# MainBoard.net
KiCad netlist of a schematic drawn in EAGLE
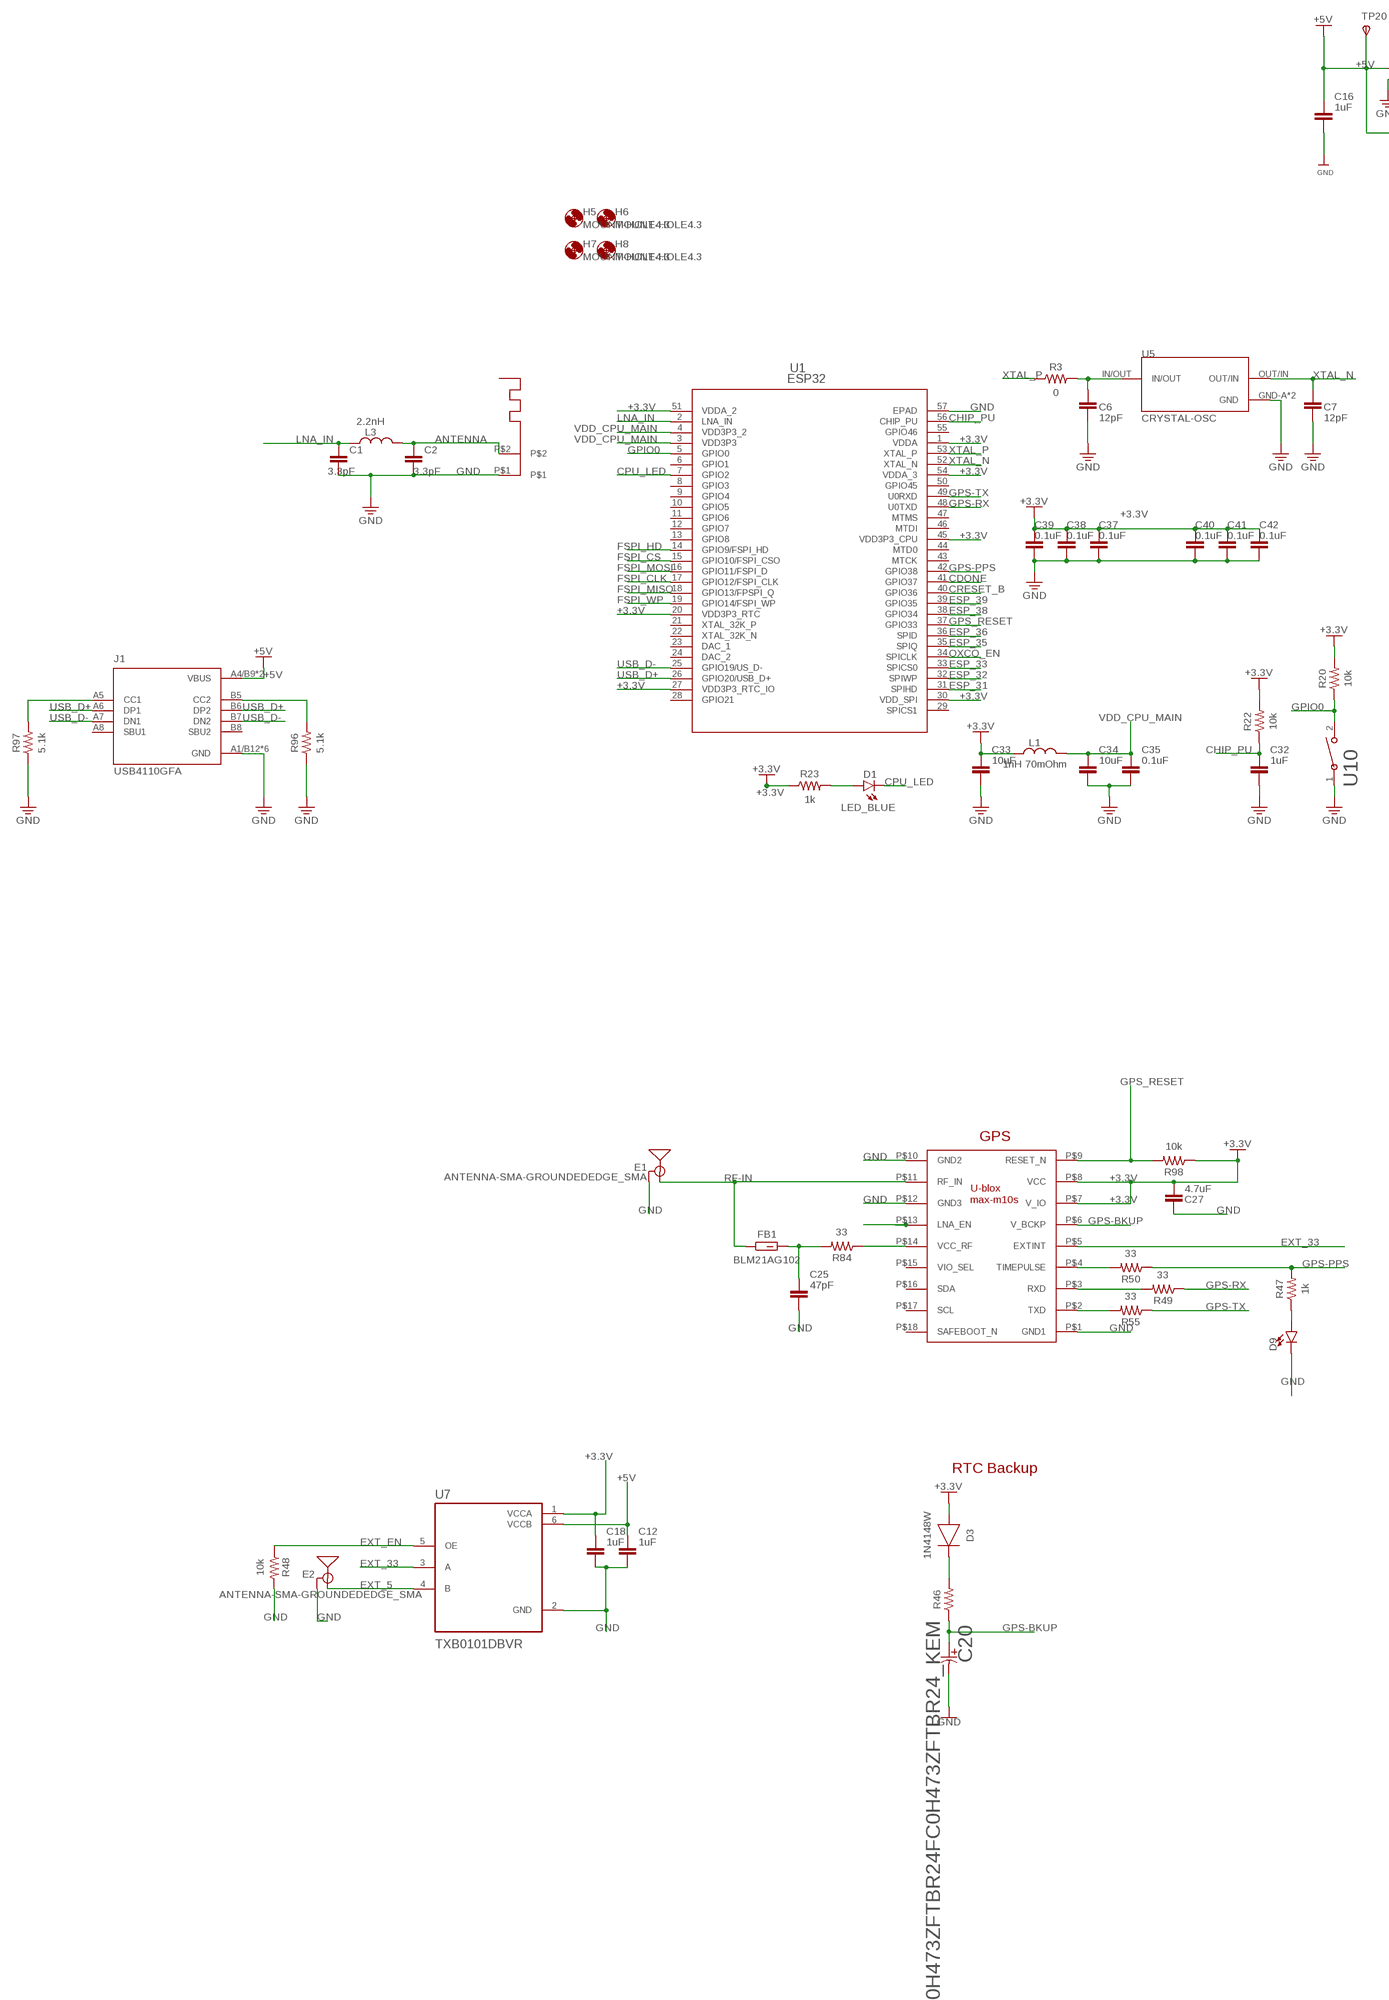
[diagram p0: schematic, sheet 1, part 1 of 2]
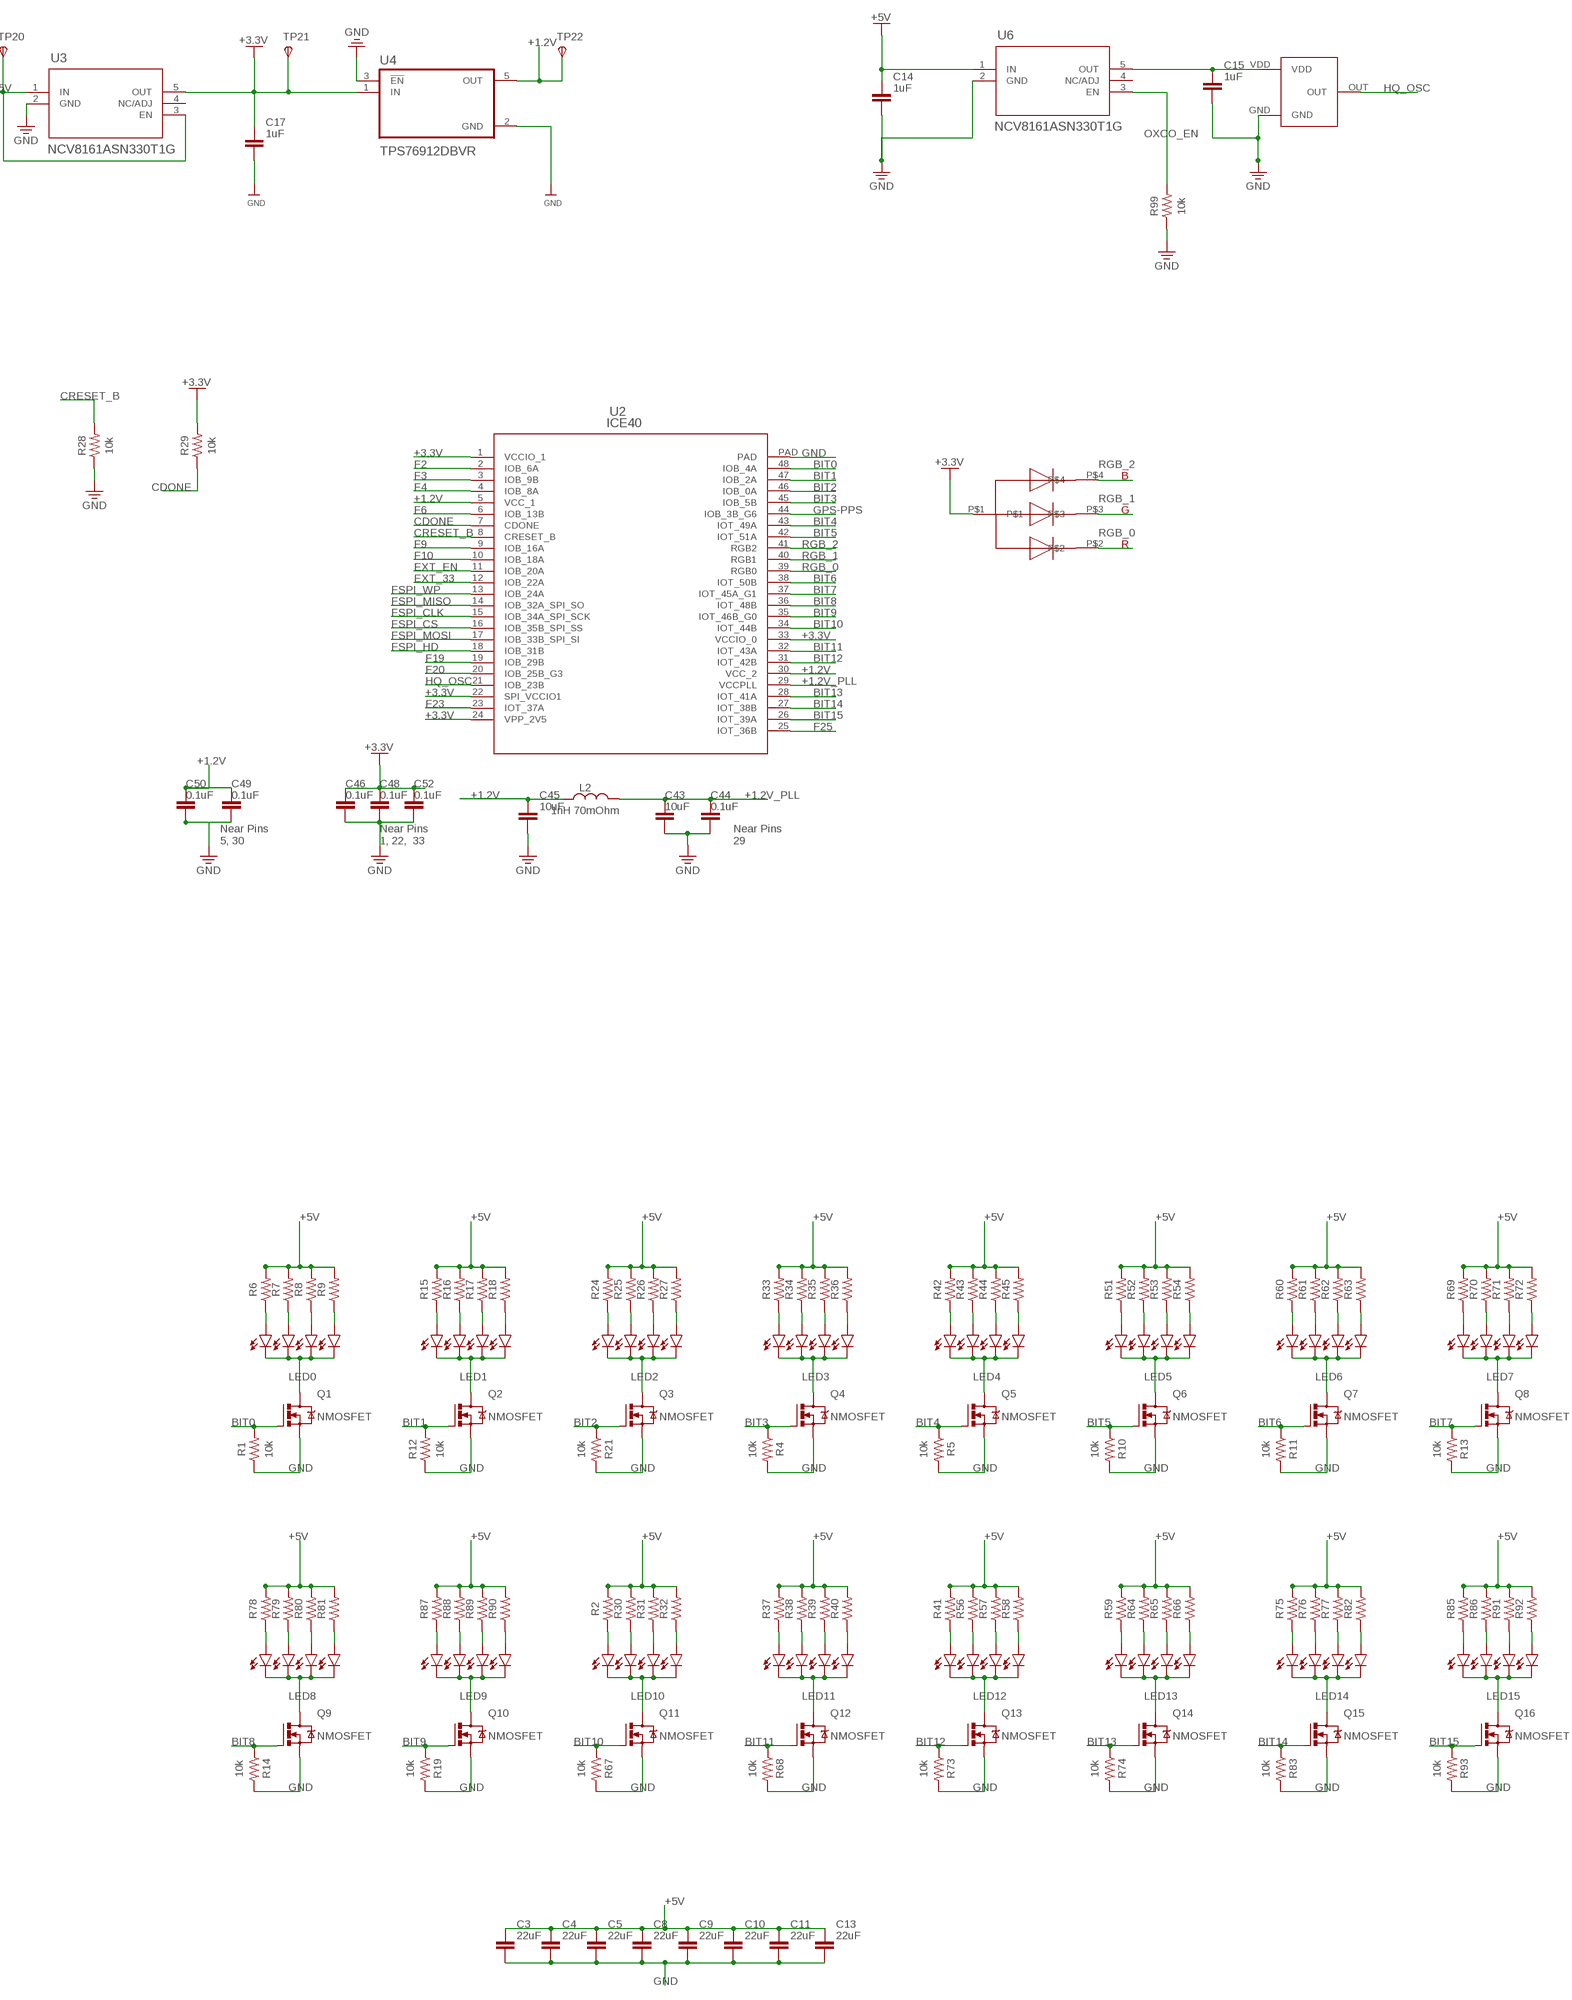
[diagram p1: schematic, sheet 1, part 2 of 2]

(export (version "E")
  (design (tool "Eeschema 10.0.6"))
  (components
    (comp (ref "C1")
      (value "3.3pF")
      (footprint "eagle-import:CAPC1005X60")
      (fields (field (name "LCSC_PART") "C76906"))
      (libsource (lib "eagle-import") (part "CCHIP-0402(1005-METRIC)_"))
    )
    (comp (ref "C2")
      (value "3.3pF")
      (footprint "eagle-import:CAPC1005X60")
      (fields (field (name "LCSC_PART") "C76906"))
      (libsource (lib "eagle-import") (part "CCHIP-0402(1005-METRIC)_"))
    )
    (comp (ref "C3")
      (value "22uF")
      (footprint "eagle-import:CAPC3225X135")
      (fields (field (name "LCSC_PART") "C52306"))
      (libsource (lib "eagle-import") (part "CCHIP-1210(3225-METRIC)_"))
    )
    (comp (ref "C4")
      (value "22uF")
      (footprint "eagle-import:CAPC3225X135")
      (fields (field (name "LCSC_PART") "C52306"))
      (libsource (lib "eagle-import") (part "CCHIP-1210(3225-METRIC)_"))
    )
    (comp (ref "C5")
      (value "22uF")
      (footprint "eagle-import:CAPC3225X135")
      (fields (field (name "LCSC_PART") "C52306"))
      (libsource (lib "eagle-import") (part "CCHIP-1210(3225-METRIC)_"))
    )
    (comp (ref "C6")
      (value "12pF")
      (footprint "eagle-import:CAPC1005X60")
      (fields (field (name "LCSC_PART") "C26406"))
      (libsource (lib "eagle-import") (part "CCHIP-0402(1005-METRIC)_"))
    )
    (comp (ref "C7")
      (value "12pF")
      (footprint "eagle-import:CAPC1005X60")
      (fields (field (name "LCSC_PART") "C26406"))
      (libsource (lib "eagle-import") (part "CCHIP-0402(1005-METRIC)_"))
    )
    (comp (ref "C8")
      (value "22uF")
      (footprint "eagle-import:CAPC3225X135")
      (fields (field (name "LCSC_PART") "C52306"))
      (libsource (lib "eagle-import") (part "CCHIP-1210(3225-METRIC)_"))
    )
    (comp (ref "C9")
      (value "22uF")
      (footprint "eagle-import:CAPC3225X135")
      (fields (field (name "LCSC_PART") "C52306"))
      (libsource (lib "eagle-import") (part "CCHIP-1210(3225-METRIC)_"))
    )
    (comp (ref "C10")
      (value "22uF")
      (footprint "eagle-import:CAPC3225X135")
      (fields (field (name "LCSC_PART") "C52306"))
      (libsource (lib "eagle-import") (part "CCHIP-1210(3225-METRIC)_"))
    )
    (comp (ref "C11")
      (value "22uF")
      (footprint "eagle-import:CAPC3225X135")
      (fields (field (name "LCSC_PART") "C52306"))
      (libsource (lib "eagle-import") (part "CCHIP-1210(3225-METRIC)_"))
    )
    (comp (ref "C12")
      (value "1uF")
      (footprint "eagle-import:CAPC1005X60")
      (fields (field (name "LCSC_PART") "C29266"))
      (libsource (lib "eagle-import") (part "CCHIP-0402(1005-METRIC)_"))
    )
    (comp (ref "C13")
      (value "22uF")
      (footprint "eagle-import:CAPC3225X135")
      (fields (field (name "LCSC_PART") "C52306"))
      (libsource (lib "eagle-import") (part "CCHIP-1210(3225-METRIC)_"))
    )
    (comp (ref "C14")
      (value "1uF")
      (footprint "eagle-import:CAPC2012X110")
      (libsource (lib "eagle-import") (part "CCHIP-0805(2012-METRIC)_"))
    )
    (comp (ref "C15")
      (value "1uF")
      (footprint "eagle-import:CAPC2012X110")
      (libsource (lib "eagle-import") (part "CCHIP-0805(2012-METRIC)_"))
    )
    (comp (ref "C16")
      (value "1uF")
      (footprint "eagle-import:CAPC2012X110")
      (libsource (lib "eagle-import") (part "CCHIP-0805(2012-METRIC)_"))
    )
    (comp (ref "C17")
      (value "1uF")
      (footprint "eagle-import:CAPC2012X110")
      (libsource (lib "eagle-import") (part "CCHIP-0805(2012-METRIC)_"))
    )
    (comp (ref "C18")
      (value "1uF")
      (footprint "eagle-import:CAPC1005X60")
      (fields (field (name "LCSC_PART") "C29266"))
      (libsource (lib "eagle-import") (part "CCHIP-0402(1005-METRIC)_"))
    )
    (comp (ref "C20")
      (value "FC0H473ZFTBR24FC0H473ZFTBR24_KEM")
      (footprint "eagle-import:FC0H473ZFTBR24_KEM")
      (fields
        (field (name "MANUFACTURER_PART_NUMBER") "FC0H473ZFTBR24")
        (field (name "COPYRIGHT") "Copyright (C) 2025 Ultra Librarian. All rights reserved.")
      )
      (libsource (lib "eagle-import") (part "FC0H473ZFTBR24FC0H473ZFTBR24_KEM"))
    )
    (comp (ref "C25")
      (value "47pF")
      (footprint "eagle-import:CAPC1005X60")
      (fields (field (name "LCSC_PART") "C1671"))
      (libsource (lib "eagle-import") (part "CCHIP-0402(1005-METRIC)_"))
    )
    (comp (ref "C27")
      (value "4.7uF")
      (footprint "eagle-import:CAPC1005X60")
      (fields (field (name "LCSC_PART") "C23733"))
      (libsource (lib "eagle-import") (part "CCHIP-0402(1005-METRIC)_"))
    )
    (comp (ref "C32")
      (value "1uF")
      (footprint "eagle-import:CAPC1005X60")
      (fields (field (name "LCSC_PART") "C29266"))
      (libsource (lib "eagle-import") (part "CCHIP-0402(1005-METRIC)_"))
    )
    (comp (ref "C33")
      (value "10uF")
      (footprint "eagle-import:CAPC1005X60")
      (fields (field (name "LCSC_PART") "C76991"))
      (libsource (lib "eagle-import") (part "CCHIP-0402(1005-METRIC)_"))
    )
    (comp (ref "C34")
      (value "10uF")
      (footprint "eagle-import:CAPC1005X60")
      (fields (field (name "LCSC_PART") "C76991"))
      (libsource (lib "eagle-import") (part "CCHIP-0402(1005-METRIC)_"))
    )
    (comp (ref "C35")
      (value "0.1uF")
      (footprint "eagle-import:CAPC1005X60")
      (fields (field (name "LCSC_PART") "C1525"))
      (libsource (lib "eagle-import") (part "CCHIP-0402(1005-METRIC)_"))
    )
    (comp (ref "C37")
      (value "0.1uF")
      (footprint "eagle-import:CAPC1005X60")
      (fields (field (name "LCSC_PART") "C1525"))
      (libsource (lib "eagle-import") (part "CCHIP-0402(1005-METRIC)_"))
    )
    (comp (ref "C38")
      (value "0.1uF")
      (footprint "eagle-import:CAPC1005X60")
      (fields (field (name "LCSC_PART") "C1525"))
      (libsource (lib "eagle-import") (part "CCHIP-0402(1005-METRIC)_"))
    )
    (comp (ref "C39")
      (value "0.1uF")
      (footprint "eagle-import:CAPC1005X60")
      (fields (field (name "LCSC_PART") "C1525"))
      (libsource (lib "eagle-import") (part "CCHIP-0402(1005-METRIC)_"))
    )
    (comp (ref "C40")
      (value "0.1uF")
      (footprint "eagle-import:CAPC1005X60")
      (fields (field (name "LCSC_PART") "C1525"))
      (libsource (lib "eagle-import") (part "CCHIP-0402(1005-METRIC)_"))
    )
    (comp (ref "C41")
      (value "0.1uF")
      (footprint "eagle-import:CAPC1005X60")
      (fields (field (name "LCSC_PART") "C1525"))
      (libsource (lib "eagle-import") (part "CCHIP-0402(1005-METRIC)_"))
    )
    (comp (ref "C42")
      (value "0.1uF")
      (footprint "eagle-import:CAPC1005X60")
      (fields (field (name "LCSC_PART") "C1525"))
      (libsource (lib "eagle-import") (part "CCHIP-0402(1005-METRIC)_"))
    )
    (comp (ref "C43")
      (value "10uF")
      (footprint "eagle-import:CAPC1005X60")
      (fields (field (name "LCSC_PART") "C76991"))
      (libsource (lib "eagle-import") (part "CCHIP-0402(1005-METRIC)_"))
    )
    (comp (ref "C44")
      (value "0.1uF")
      (footprint "eagle-import:CAPC1005X60")
      (fields (field (name "LCSC_PART") "C1525"))
      (libsource (lib "eagle-import") (part "CCHIP-0402(1005-METRIC)_"))
    )
    (comp (ref "C45")
      (value "10uF")
      (footprint "eagle-import:CAPC1005X60")
      (fields (field (name "LCSC_PART") "C76991"))
      (libsource (lib "eagle-import") (part "CCHIP-0402(1005-METRIC)_"))
    )
    (comp (ref "C46")
      (value "0.1uF")
      (footprint "eagle-import:CAPC1005X60")
      (fields (field (name "LCSC_PART") "C1525"))
      (libsource (lib "eagle-import") (part "CCHIP-0402(1005-METRIC)_"))
    )
    (comp (ref "C48")
      (value "0.1uF")
      (footprint "eagle-import:CAPC1005X60")
      (fields (field (name "LCSC_PART") "C1525"))
      (libsource (lib "eagle-import") (part "CCHIP-0402(1005-METRIC)_"))
    )
    (comp (ref "C49")
      (value "0.1uF")
      (footprint "eagle-import:CAPC1005X60")
      (fields (field (name "LCSC_PART") "C1525"))
      (libsource (lib "eagle-import") (part "CCHIP-0402(1005-METRIC)_"))
    )
    (comp (ref "C50")
      (value "0.1uF")
      (footprint "eagle-import:CAPC1005X60")
      (fields (field (name "LCSC_PART") "C1525"))
      (libsource (lib "eagle-import") (part "CCHIP-0402(1005-METRIC)_"))
    )
    (comp (ref "C52")
      (value "0.1uF")
      (footprint "eagle-import:CAPC1005X60")
      (fields (field (name "LCSC_PART") "C1525"))
      (libsource (lib "eagle-import") (part "CCHIP-0402(1005-METRIC)_"))
    )
    (comp (ref "D1")
      (value "LED_BLUE")
      (footprint "eagle-import:LEDC1005X25N_FLAT-B")
      (fields (field (name "LCSC_PART") "C22355736"))
      (libsource (lib "eagle-import") (part "CHIP-FLAT-B_0402"))
    )
    (comp (ref "D2")
      (value "LED_BLUE")
      (footprint "eagle-import:LEDC3216X180N_RND-B")
      (libsource (lib "eagle-import") (part "CHIP-ROUND-B_1206"))
    )
    (comp (ref "D3")
      (value "1N4148W")
      (footprint "eagle-import:SOD3715X135")
      (fields (field (name "MANUFACTURER") "Diodes Incorporated") (field (name "LCSC_PART") "C2128"))
      (libsource (lib "eagle-import") (part "DIODE__SOD123G1N4148W-7-F"))
    )
    (comp (ref "D4")
      (value "LED_BLUE")
      (footprint "eagle-import:LEDC3216X180N_RND-B")
      (fields (field (name "LCSC_PART") "C375482"))
      (libsource (lib "eagle-import") (part "CHIP-ROUND-B_1206"))
    )
    (comp (ref "D5")
      (value "LED_BLUE")
      (footprint "eagle-import:LEDC3216X180N_RND-B")
      (libsource (lib "eagle-import") (part "CHIP-ROUND-B_1206"))
    )
    (comp (ref "D6")
      (value "LED_BLUE")
      (footprint "eagle-import:LEDC3216X180N_RND-B")
      (libsource (lib "eagle-import") (part "CHIP-ROUND-B_1206"))
    )
    (comp (ref "D7")
      (value "LED_BLUE")
      (footprint "eagle-import:LEDC3216X180N_RND-B")
      (libsource (lib "eagle-import") (part "CHIP-ROUND-B_1206"))
    )
    (comp (ref "D8")
      (value "LED_BLUE")
      (footprint "eagle-import:LEDC3216X180N_RND-B")
      (libsource (lib "eagle-import") (part "CHIP-ROUND-B_1206"))
    )
    (comp (ref "D9")
      (value "LED0603")
      (footprint "eagle-import:LED-0603")
      (fields (field (name "LCSC_PART") "C2286"))
      (libsource (lib "eagle-import") (part "LED0603"))
    )
    (comp (ref "D10")
      (value "LED_BLUE")
      (footprint "eagle-import:LEDC3216X180N_RND-B")
      (libsource (lib "eagle-import") (part "CHIP-ROUND-B_1206"))
    )
    (comp (ref "D11")
      (value "LED_BLUE")
      (footprint "eagle-import:LEDC3216X180N_RND-B")
      (libsource (lib "eagle-import") (part "CHIP-ROUND-B_1206"))
    )
    (comp (ref "D12")
      (value "LED_BLUE")
      (footprint "eagle-import:LEDC3216X180N_RND-B")
      (libsource (lib "eagle-import") (part "CHIP-ROUND-B_1206"))
    )
    (comp (ref "D13")
      (value "LED_BLUE")
      (footprint "eagle-import:LEDC3216X180N_RND-B")
      (libsource (lib "eagle-import") (part "CHIP-ROUND-B_1206"))
    )
    (comp (ref "D14")
      (value "LED_BLUE")
      (footprint "eagle-import:LEDC3216X180N_RND-B")
      (libsource (lib "eagle-import") (part "CHIP-ROUND-B_1206"))
    )
    (comp (ref "D15")
      (value "LED_BLUE")
      (footprint "eagle-import:LEDC3216X180N_RND-B")
      (libsource (lib "eagle-import") (part "CHIP-ROUND-B_1206"))
    )
    (comp (ref "D16")
      (value "LED_BLUE")
      (footprint "eagle-import:LEDC3216X180N_RND-B")
      (libsource (lib "eagle-import") (part "CHIP-ROUND-B_1206"))
    )
    (comp (ref "D17")
      (value "LED_BLUE")
      (footprint "eagle-import:LEDC3216X180N_RND-B")
      (libsource (lib "eagle-import") (part "CHIP-ROUND-B_1206"))
    )
    (comp (ref "D18")
      (value "LED_BLUE")
      (footprint "eagle-import:LEDC3216X180N_RND-B")
      (libsource (lib "eagle-import") (part "CHIP-ROUND-B_1206"))
    )
    (comp (ref "D19")
      (value "LED_BLUE")
      (footprint "eagle-import:LEDC3216X180N_RND-B")
      (libsource (lib "eagle-import") (part "CHIP-ROUND-B_1206"))
    )
    (comp (ref "D20")
      (value "LED_BLUE")
      (footprint "eagle-import:LEDC3216X180N_RND-B")
      (libsource (lib "eagle-import") (part "CHIP-ROUND-B_1206"))
    )
    (comp (ref "D21")
      (value "LED_BLUE")
      (footprint "eagle-import:LEDC3216X180N_RND-B")
      (libsource (lib "eagle-import") (part "CHIP-ROUND-B_1206"))
    )
    (comp (ref "D22")
      (value "LED_BLUE")
      (footprint "eagle-import:LEDC3216X180N_RND-B")
      (libsource (lib "eagle-import") (part "CHIP-ROUND-B_1206"))
    )
    (comp (ref "D23")
      (value "LED_BLUE")
      (footprint "eagle-import:LEDC3216X180N_RND-B")
      (libsource (lib "eagle-import") (part "CHIP-ROUND-B_1206"))
    )
    (comp (ref "D24")
      (value "LED_BLUE")
      (footprint "eagle-import:LEDC3216X180N_RND-B")
      (libsource (lib "eagle-import") (part "CHIP-ROUND-B_1206"))
    )
    (comp (ref "D25")
      (value "LED_BLUE")
      (footprint "eagle-import:LEDC3216X180N_RND-B")
      (libsource (lib "eagle-import") (part "CHIP-ROUND-B_1206"))
    )
    (comp (ref "D26")
      (value "LED_BLUE")
      (footprint "eagle-import:LEDC3216X180N_RND-B")
      (libsource (lib "eagle-import") (part "CHIP-ROUND-B_1206"))
    )
    (comp (ref "D27")
      (value "LED_BLUE")
      (footprint "eagle-import:LEDC3216X180N_RND-B")
      (libsource (lib "eagle-import") (part "CHIP-ROUND-B_1206"))
    )
    (comp (ref "D28")
      (value "LED_BLUE")
      (footprint "eagle-import:LEDC3216X180N_RND-B")
      (libsource (lib "eagle-import") (part "CHIP-ROUND-B_1206"))
    )
    (comp (ref "D29")
      (value "LED_BLUE")
      (footprint "eagle-import:LEDC3216X180N_RND-B")
      (libsource (lib "eagle-import") (part "CHIP-ROUND-B_1206"))
    )
    (comp (ref "D30")
      (value "LED_BLUE")
      (footprint "eagle-import:LEDC3216X180N_RND-B")
      (libsource (lib "eagle-import") (part "CHIP-ROUND-B_1206"))
    )
    (comp (ref "D31")
      (value "LED_BLUE")
      (footprint "eagle-import:LEDC3216X180N_RND-B")
      (libsource (lib "eagle-import") (part "CHIP-ROUND-B_1206"))
    )
    (comp (ref "D32")
      (value "LED_BLUE")
      (footprint "eagle-import:LEDC3216X180N_RND-B")
      (libsource (lib "eagle-import") (part "CHIP-ROUND-B_1206"))
    )
    (comp (ref "D33")
      (value "LED_BLUE")
      (footprint "eagle-import:LEDC3216X180N_RND-B")
      (libsource (lib "eagle-import") (part "CHIP-ROUND-B_1206"))
    )
    (comp (ref "D34")
      (value "LED_BLUE")
      (footprint "eagle-import:LEDC3216X180N_RND-B")
      (libsource (lib "eagle-import") (part "CHIP-ROUND-B_1206"))
    )
    (comp (ref "D35")
      (value "LED_BLUE")
      (footprint "eagle-import:LEDC3216X180N_RND-B")
      (libsource (lib "eagle-import") (part "CHIP-ROUND-B_1206"))
    )
    (comp (ref "D36")
      (value "LED_BLUE")
      (footprint "eagle-import:LEDC3216X180N_RND-B")
      (libsource (lib "eagle-import") (part "CHIP-ROUND-B_1206"))
    )
    (comp (ref "D37")
      (value "LED_BLUE")
      (footprint "eagle-import:LEDC3216X180N_RND-B")
      (libsource (lib "eagle-import") (part "CHIP-ROUND-B_1206"))
    )
    (comp (ref "D38")
      (value "LED_BLUE")
      (footprint "eagle-import:LEDC3216X180N_RND-B")
      (libsource (lib "eagle-import") (part "CHIP-ROUND-B_1206"))
    )
    (comp (ref "D39")
      (value "LED_BLUE")
      (footprint "eagle-import:LEDC3216X180N_RND-B")
      (libsource (lib "eagle-import") (part "CHIP-ROUND-B_1206"))
    )
    (comp (ref "D40")
      (value "LED_BLUE")
      (footprint "eagle-import:LEDC3216X180N_RND-B")
      (libsource (lib "eagle-import") (part "CHIP-ROUND-B_1206"))
    )
    (comp (ref "D41")
      (value "LED_BLUE")
      (footprint "eagle-import:LEDC3216X180N_RND-B")
      (libsource (lib "eagle-import") (part "CHIP-ROUND-B_1206"))
    )
    (comp (ref "D42")
      (value "LED_BLUE")
      (footprint "eagle-import:LEDC3216X180N_RND-B")
      (libsource (lib "eagle-import") (part "CHIP-ROUND-B_1206"))
    )
    (comp (ref "D43")
      (value "LED_BLUE")
      (footprint "eagle-import:LEDC3216X180N_RND-B")
      (libsource (lib "eagle-import") (part "CHIP-ROUND-B_1206"))
    )
    (comp (ref "D44")
      (value "LED_BLUE")
      (footprint "eagle-import:LEDC3216X180N_RND-B")
      (libsource (lib "eagle-import") (part "CHIP-ROUND-B_1206"))
    )
    (comp (ref "D45")
      (value "LED_BLUE")
      (footprint "eagle-import:LEDC3216X180N_RND-B")
      (libsource (lib "eagle-import") (part "CHIP-ROUND-B_1206"))
    )
    (comp (ref "D46")
      (value "LED_BLUE")
      (footprint "eagle-import:LEDC3216X180N_RND-B")
      (libsource (lib "eagle-import") (part "CHIP-ROUND-B_1206"))
    )
    (comp (ref "D47")
      (value "LED_BLUE")
      (footprint "eagle-import:LEDC3216X180N_RND-B")
      (libsource (lib "eagle-import") (part "CHIP-ROUND-B_1206"))
    )
    (comp (ref "D48")
      (value "LED_BLUE")
      (footprint "eagle-import:LEDC3216X180N_RND-B")
      (libsource (lib "eagle-import") (part "CHIP-ROUND-B_1206"))
    )
    (comp (ref "D49")
      (value "LED_BLUE")
      (footprint "eagle-import:LEDC3216X180N_RND-B")
      (libsource (lib "eagle-import") (part "CHIP-ROUND-B_1206"))
    )
    (comp (ref "D50")
      (value "LED_BLUE")
      (footprint "eagle-import:LEDC3216X180N_RND-B")
      (libsource (lib "eagle-import") (part "CHIP-ROUND-B_1206"))
    )
    (comp (ref "D51")
      (value "LED_BLUE")
      (footprint "eagle-import:LEDC3216X180N_RND-B")
      (libsource (lib "eagle-import") (part "CHIP-ROUND-B_1206"))
    )
    (comp (ref "D52")
      (value "LED_BLUE")
      (footprint "eagle-import:LEDC3216X180N_RND-B")
      (libsource (lib "eagle-import") (part "CHIP-ROUND-B_1206"))
    )
    (comp (ref "D53")
      (value "LED_BLUE")
      (footprint "eagle-import:LEDC3216X180N_RND-B")
      (libsource (lib "eagle-import") (part "CHIP-ROUND-B_1206"))
    )
    (comp (ref "D54")
      (value "LED_BLUE")
      (footprint "eagle-import:LEDC3216X180N_RND-B")
      (libsource (lib "eagle-import") (part "CHIP-ROUND-B_1206"))
    )
    (comp (ref "D55")
      (value "LED_BLUE")
      (footprint "eagle-import:LEDC3216X180N_RND-B")
      (libsource (lib "eagle-import") (part "CHIP-ROUND-B_1206"))
    )
    (comp (ref "D60")
      (value "LED_BLUE")
      (footprint "eagle-import:LEDC3216X180N_RND-B")
      (libsource (lib "eagle-import") (part "CHIP-ROUND-B_1206"))
    )
    (comp (ref "D61")
      (value "LED_BLUE")
      (footprint "eagle-import:LEDC3216X180N_RND-B")
      (libsource (lib "eagle-import") (part "CHIP-ROUND-B_1206"))
    )
    (comp (ref "D62")
      (value "LED_BLUE")
      (footprint "eagle-import:LEDC3216X180N_RND-B")
      (libsource (lib "eagle-import") (part "CHIP-ROUND-B_1206"))
    )
    (comp (ref "D63")
      (value "LED_BLUE")
      (footprint "eagle-import:LEDC3216X180N_RND-B")
      (libsource (lib "eagle-import") (part "CHIP-ROUND-B_1206"))
    )
    (comp (ref "D68")
      (value "LED_BLUE")
      (footprint "eagle-import:LEDC3216X180N_RND-B")
      (libsource (lib "eagle-import") (part "CHIP-ROUND-B_1206"))
    )
    (comp (ref "D69")
      (value "LED_BLUE")
      (footprint "eagle-import:LEDC3216X180N_RND-B")
      (libsource (lib "eagle-import") (part "CHIP-ROUND-B_1206"))
    )
    (comp (ref "D70")
      (value "LED_BLUE")
      (footprint "eagle-import:LEDC3216X180N_RND-B")
      (libsource (lib "eagle-import") (part "CHIP-ROUND-B_1206"))
    )
    (comp (ref "D71")
      (value "LED_BLUE")
      (footprint "eagle-import:LEDC3216X180N_RND-B")
      (libsource (lib "eagle-import") (part "CHIP-ROUND-B_1206"))
    )
    (comp (ref "D76")
      (value "LED_BLUE")
      (footprint "eagle-import:LEDC3216X180N_RND-B")
      (libsource (lib "eagle-import") (part "CHIP-ROUND-B_1206"))
    )
    (comp (ref "D77")
      (value "LED_BLUE")
      (footprint "eagle-import:LEDC3216X180N_RND-B")
      (libsource (lib "eagle-import") (part "CHIP-ROUND-B_1206"))
    )
    (comp (ref "D78")
      (value "LED_BLUE")
      (footprint "eagle-import:LEDC3216X180N_RND-B")
      (libsource (lib "eagle-import") (part "CHIP-ROUND-B_1206"))
    )
    (comp (ref "D79")
      (value "LED_BLUE")
      (footprint "eagle-import:LEDC3216X180N_RND-B")
      (libsource (lib "eagle-import") (part "CHIP-ROUND-B_1206"))
    )
    (comp (ref "E1")
      (value "ANTENNA-SMA-GROUNDEDEDGE_SMA")
      (footprint "eagle-import:SMA-EDGE")
      (libsource (lib "eagle-import") (part "ANTENNA-SMA-GROUNDEDEDGE_SMA"))
    )
    (comp (ref "E2")
      (value "ANTENNA-SMA-GROUNDEDEDGE_SMA")
      (footprint "eagle-import:SMA-EDGE")
      (libsource (lib "eagle-import") (part "ANTENNA-SMA-GROUNDEDEDGE_SMA"))
    )
    (comp (ref "FB1")
      (value "BLM21AG102")
      (footprint "eagle-import:BEADC2012X105N")
      (fields (field (name "MANUFACTURER") "Murata Electronics") (field (name "LCSC_PART") "C76817"))
      (libsource (lib "eagle-import") (part "FB__0805(2012)BLM21AG102SN1D"))
    )
    (comp (ref "H5")
      (value "MOUNT-HOLE4.3")
      (footprint "eagle-import:4,3")
      (libsource (lib "eagle-import") (part "MOUNT-HOLE4.3"))
    )
    (comp (ref "H6")
      (value "MOUNT-HOLE4.3")
      (footprint "eagle-import:4,3")
      (libsource (lib "eagle-import") (part "MOUNT-HOLE4.3"))
    )
    (comp (ref "H7")
      (value "MOUNT-HOLE4.3")
      (footprint "eagle-import:4,3")
      (libsource (lib "eagle-import") (part "MOUNT-HOLE4.3"))
    )
    (comp (ref "H8")
      (value "MOUNT-HOLE4.3")
      (footprint "eagle-import:4,3")
      (libsource (lib "eagle-import") (part "MOUNT-HOLE4.3"))
    )
    (comp (ref "J1")
      (value "USB4110GFA")
      (footprint "eagle-import:GCT_USB4110GFA")
      (fields (field (name "MF") "GCT") (field (name "LCSC_PART") "C34260841"))
      (libsource (lib "eagle-import") (part "USB4110GFA"))
    )
    (comp (ref "L1")
      (value "1nH 70mOhm")
      (footprint "eagle-import:INDC1006X60N")
      (fields (field (name "MPN") "BLM18KG101TN1D") (field (name "LCSC_PART") "C18222"))
      (libsource (lib "eagle-import") (part "LCHIP-0402(1006-METRIC)_"))
    )
    (comp (ref "L2")
      (value "1nH 70mOhm")
      (footprint "eagle-import:INDC1006X60N")
      (fields (field (name "MPN") "BLM18KG101TN1D") (field (name "LCSC_PART") "C18222"))
      (libsource (lib "eagle-import") (part "LCHIP-0402(1006-METRIC)_"))
    )
    (comp (ref "L3")
      (value "2.2nH")
      (footprint "eagle-import:INDC1006X60N")
      (fields (field (name "MPN") "BLM18KG101TN1D") (field (name "LCSC_PART") "C86061"))
      (libsource (lib "eagle-import") (part "LCHIP-0402(1006-METRIC)_"))
    )
    (comp (ref "Q1")
      (value "NMOSFET")
      (footprint "eagle-import:SOT23")
      (fields (field (name "LCSC_PART") "C478010"))
      (libsource (lib "eagle-import") (part "NMOSFETSOT23-GSD"))
    )
    (comp (ref "Q2")
      (value "NMOSFET")
      (footprint "eagle-import:SOT23")
      (fields (field (name "LCSC_PART") "C478010"))
      (libsource (lib "eagle-import") (part "NMOSFETSOT23-GSD"))
    )
    (comp (ref "Q3")
      (value "NMOSFET")
      (footprint "eagle-import:SOT23")
      (fields (field (name "LCSC_PART") "C478010"))
      (libsource (lib "eagle-import") (part "NMOSFETSOT23-GSD"))
    )
    (comp (ref "Q4")
      (value "NMOSFET")
      (footprint "eagle-import:SOT23")
      (fields (field (name "LCSC_PART") "C478010"))
      (libsource (lib "eagle-import") (part "NMOSFETSOT23-GSD"))
    )
    (comp (ref "Q5")
      (value "NMOSFET")
      (footprint "eagle-import:SOT23")
      (fields (field (name "LCSC_PART") "C478010"))
      (libsource (lib "eagle-import") (part "NMOSFETSOT23-GSD"))
    )
    (comp (ref "Q6")
      (value "NMOSFET")
      (footprint "eagle-import:SOT23")
      (fields (field (name "LCSC_PART") "C478010"))
      (libsource (lib "eagle-import") (part "NMOSFETSOT23-GSD"))
    )
    (comp (ref "Q7")
      (value "NMOSFET")
      (footprint "eagle-import:SOT23")
      (fields (field (name "LCSC_PART") "C478010"))
      (libsource (lib "eagle-import") (part "NMOSFETSOT23-GSD"))
    )
    (comp (ref "Q8")
      (value "NMOSFET")
      (footprint "eagle-import:SOT23")
      (fields (field (name "LCSC_PART") "C478010"))
      (libsource (lib "eagle-import") (part "NMOSFETSOT23-GSD"))
    )
    (comp (ref "Q9")
      (value "NMOSFET")
      (footprint "eagle-import:SOT23")
      (fields (field (name "LCSC_PART") "C478010"))
      (libsource (lib "eagle-import") (part "NMOSFETSOT23-GSD"))
    )
    (comp (ref "Q10")
      (value "NMOSFET")
      (footprint "eagle-import:SOT23")
      (fields (field (name "LCSC_PART") "C478010"))
      (libsource (lib "eagle-import") (part "NMOSFETSOT23-GSD"))
    )
    (comp (ref "Q11")
      (value "NMOSFET")
      (footprint "eagle-import:SOT23")
      (fields (field (name "LCSC_PART") "C478010"))
      (libsource (lib "eagle-import") (part "NMOSFETSOT23-GSD"))
    )
    (comp (ref "Q12")
      (value "NMOSFET")
      (footprint "eagle-import:SOT23")
      (fields (field (name "LCSC_PART") "C478010"))
      (libsource (lib "eagle-import") (part "NMOSFETSOT23-GSD"))
    )
    (comp (ref "Q13")
      (value "NMOSFET")
      (footprint "eagle-import:SOT23")
      (fields (field (name "LCSC_PART") "C478010"))
      (libsource (lib "eagle-import") (part "NMOSFETSOT23-GSD"))
    )
    (comp (ref "Q14")
      (value "NMOSFET")
      (footprint "eagle-import:SOT23")
      (fields (field (name "LCSC_PART") "C478010"))
      (libsource (lib "eagle-import") (part "NMOSFETSOT23-GSD"))
    )
    (comp (ref "Q15")
      (value "NMOSFET")
      (footprint "eagle-import:SOT23")
      (fields (field (name "LCSC_PART") "C478010"))
      (libsource (lib "eagle-import") (part "NMOSFETSOT23-GSD"))
    )
    (comp (ref "Q16")
      (value "NMOSFET")
      (footprint "eagle-import:SOT23")
      (fields (field (name "LCSC_PART") "C478010"))
      (libsource (lib "eagle-import") (part "NMOSFETSOT23-GSD"))
    )
    (comp (ref "R1")
      (value "10k")
      (footprint "eagle-import:RESC2012X65")
      (fields (field (name "LCSC_PART") "C60490"))
      (libsource (lib "eagle-import") (part "Resistor_16378527_R-USCHIP-0805(2012-METRIC)_"))
    )
    (comp (ref "R2")
      (value "R-US_CHIP-0805(2012-METRIC)")
      (footprint "eagle-import:RESC2012X65")
      (libsource (lib "eagle-import") (part "R-USCHIP-0805(2012-METRIC)_"))
    )
    (comp (ref "R3")
      (value "0")
      (footprint "eagle-import:RESC1005X40")
      (fields (field (name "LCSC_PART") "C17168"))
      (libsource (lib "eagle-import") (part "Resistor_16378527_R-USCHIP-0402(1005-METRIC)_"))
    )
    (comp (ref "R4")
      (value "10k")
      (footprint "eagle-import:RESC2012X65")
      (fields (field (name "LCSC_PART") "C60490"))
      (libsource (lib "eagle-import") (part "Resistor_16378527_R-USCHIP-0805(2012-METRIC)_"))
    )
    (comp (ref "R5")
      (value "10k")
      (footprint "eagle-import:RESC2012X65")
      (fields (field (name "LCSC_PART") "C60490"))
      (libsource (lib "eagle-import") (part "Resistor_16378527_R-USCHIP-0805(2012-METRIC)_"))
    )
    (comp (ref "R6")
      (value "R-US_CHIP-0805(2012-METRIC)")
      (footprint "eagle-import:RESC2012X65")
      (libsource (lib "eagle-import") (part "R-USCHIP-0805(2012-METRIC)_"))
    )
    (comp (ref "R7")
      (value "R-US_CHIP-0805(2012-METRIC)")
      (footprint "eagle-import:RESC2012X65")
      (libsource (lib "eagle-import") (part "R-USCHIP-0805(2012-METRIC)_"))
    )
    (comp (ref "R8")
      (value "R-US_CHIP-0805(2012-METRIC)")
      (footprint "eagle-import:RESC2012X65")
      (libsource (lib "eagle-import") (part "R-USCHIP-0805(2012-METRIC)_"))
    )
    (comp (ref "R9")
      (value "R-US_CHIP-0805(2012-METRIC)")
      (footprint "eagle-import:RESC2012X65")
      (libsource (lib "eagle-import") (part "R-USCHIP-0805(2012-METRIC)_"))
    )
    (comp (ref "R10")
      (value "10k")
      (footprint "eagle-import:RESC2012X65")
      (fields (field (name "LCSC_PART") "C60490"))
      (libsource (lib "eagle-import") (part "Resistor_16378527_R-USCHIP-0805(2012-METRIC)_"))
    )
    (comp (ref "R11")
      (value "10k")
      (footprint "eagle-import:RESC2012X65")
      (fields (field (name "LCSC_PART") "C60490"))
      (libsource (lib "eagle-import") (part "Resistor_16378527_R-USCHIP-0805(2012-METRIC)_"))
    )
    (comp (ref "R12")
      (value "10k")
      (footprint "eagle-import:RESC2012X65")
      (fields (field (name "LCSC_PART") "C60490"))
      (libsource (lib "eagle-import") (part "Resistor_16378527_R-USCHIP-0805(2012-METRIC)_"))
    )
    (comp (ref "R13")
      (value "10k")
      (footprint "eagle-import:RESC2012X65")
      (fields (field (name "LCSC_PART") "C60490"))
      (libsource (lib "eagle-import") (part "Resistor_16378527_R-USCHIP-0805(2012-METRIC)_"))
    )
    (comp (ref "R14")
      (value "10k")
      (footprint "eagle-import:RESC2012X65")
      (fields (field (name "LCSC_PART") "C60490"))
      (libsource (lib "eagle-import") (part "Resistor_16378527_R-USCHIP-0805(2012-METRIC)_"))
    )
    (comp (ref "R15")
      (value "R-US_CHIP-0805(2012-METRIC)")
      (footprint "eagle-import:RESC2012X65")
      (libsource (lib "eagle-import") (part "R-USCHIP-0805(2012-METRIC)_"))
    )
    (comp (ref "R16")
      (value "R-US_CHIP-0805(2012-METRIC)")
      (footprint "eagle-import:RESC2012X65")
      (libsource (lib "eagle-import") (part "R-USCHIP-0805(2012-METRIC)_"))
    )
    (comp (ref "R17")
      (value "R-US_CHIP-0805(2012-METRIC)")
      (footprint "eagle-import:RESC2012X65")
      (libsource (lib "eagle-import") (part "R-USCHIP-0805(2012-METRIC)_"))
    )
    (comp (ref "R18")
      (value "R-US_CHIP-0805(2012-METRIC)")
      (footprint "eagle-import:RESC2012X65")
      (libsource (lib "eagle-import") (part "R-USCHIP-0805(2012-METRIC)_"))
    )
    (comp (ref "R19")
      (value "10k")
      (footprint "eagle-import:RESC2012X65")
      (fields (field (name "LCSC_PART") "C60490"))
      (libsource (lib "eagle-import") (part "Resistor_16378527_R-USCHIP-0805(2012-METRIC)_"))
    )
    (comp (ref "R20")
      (value "10k")
      (footprint "eagle-import:RESC1005X40")
      (fields (field (name "LCSC_PART") "C60490"))
      (libsource (lib "eagle-import") (part "Resistor_16378527_R-USCHIP-0402(1005-METRIC)_"))
    )
    (comp (ref "R21")
      (value "10k")
      (footprint "eagle-import:RESC2012X65")
      (fields (field (name "LCSC_PART") "C60490"))
      (libsource (lib "eagle-import") (part "Resistor_16378527_R-USCHIP-0805(2012-METRIC)_"))
    )
    (comp (ref "R22")
      (value "10k")
      (footprint "eagle-import:RESC1005X40")
      (fields (field (name "LCSC_PART") "C60490"))
      (libsource (lib "eagle-import") (part "Resistor_16378527_R-USCHIP-0402(1005-METRIC)_"))
    )
    (comp (ref "R23")
      (value "1k")
      (footprint "eagle-import:RESC1005X40")
      (fields (field (name "LCSC_PART") "C11702"))
      (libsource (lib "eagle-import") (part "Resistor_16378527_R-USCHIP-0402(1005-METRIC)_"))
    )
    (comp (ref "R24")
      (value "R-US_CHIP-0805(2012-METRIC)")
      (footprint "eagle-import:RESC2012X65")
      (libsource (lib "eagle-import") (part "R-USCHIP-0805(2012-METRIC)_"))
    )
    (comp (ref "R25")
      (value "R-US_CHIP-0805(2012-METRIC)")
      (footprint "eagle-import:RESC2012X65")
      (libsource (lib "eagle-import") (part "R-USCHIP-0805(2012-METRIC)_"))
    )
    (comp (ref "R26")
      (value "R-US_CHIP-0805(2012-METRIC)")
      (footprint "eagle-import:RESC2012X65")
      (libsource (lib "eagle-import") (part "R-USCHIP-0805(2012-METRIC)_"))
    )
    (comp (ref "R27")
      (value "R-US_CHIP-0805(2012-METRIC)")
      (footprint "eagle-import:RESC2012X65")
      (libsource (lib "eagle-import") (part "R-USCHIP-0805(2012-METRIC)_"))
    )
    (comp (ref "R28")
      (value "10k")
      (footprint "eagle-import:RESC1005X40")
      (fields (field (name "LCSC_PART") "C60490"))
      (libsource (lib "eagle-import") (part "Resistor_16378527_R-USCHIP-0402(1005-METRIC)_"))
    )
    (comp (ref "R29")
      (value "10k")
      (footprint "eagle-import:RESC1005X40")
      (fields (field (name "LCSC_PART") "C60490"))
      (libsource (lib "eagle-import") (part "Resistor_16378527_R-USCHIP-0402(1005-METRIC)_"))
    )
    (comp (ref "R30")
      (value "R-US_CHIP-0805(2012-METRIC)")
      (footprint "eagle-import:RESC2012X65")
      (libsource (lib "eagle-import") (part "R-USCHIP-0805(2012-METRIC)_"))
    )
    (comp (ref "R31")
      (value "R-US_CHIP-0805(2012-METRIC)")
      (footprint "eagle-import:RESC2012X65")
      (libsource (lib "eagle-import") (part "R-USCHIP-0805(2012-METRIC)_"))
    )
    (comp (ref "R32")
      (value "R-US_CHIP-0805(2012-METRIC)")
      (footprint "eagle-import:RESC2012X65")
      (libsource (lib "eagle-import") (part "R-USCHIP-0805(2012-METRIC)_"))
    )
    (comp (ref "R33")
      (value "R-US_CHIP-0805(2012-METRIC)")
      (footprint "eagle-import:RESC2012X65")
      (libsource (lib "eagle-import") (part "R-USCHIP-0805(2012-METRIC)_"))
    )
    (comp (ref "R34")
      (value "R-US_CHIP-0805(2012-METRIC)")
      (footprint "eagle-import:RESC2012X65")
      (libsource (lib "eagle-import") (part "R-USCHIP-0805(2012-METRIC)_"))
    )
    (comp (ref "R35")
      (value "R-US_CHIP-0805(2012-METRIC)")
      (footprint "eagle-import:RESC2012X65")
      (libsource (lib "eagle-import") (part "R-USCHIP-0805(2012-METRIC)_"))
    )
    (comp (ref "R36")
      (value "R-US_CHIP-0805(2012-METRIC)")
      (footprint "eagle-import:RESC2012X65")
      (libsource (lib "eagle-import") (part "R-USCHIP-0805(2012-METRIC)_"))
    )
    (comp (ref "R37")
      (value "R-US_CHIP-0805(2012-METRIC)")
      (footprint "eagle-import:RESC2012X65")
      (libsource (lib "eagle-import") (part "R-USCHIP-0805(2012-METRIC)_"))
    )
    (comp (ref "R38")
      (value "R-US_CHIP-0805(2012-METRIC)")
      (footprint "eagle-import:RESC2012X65")
      (libsource (lib "eagle-import") (part "R-USCHIP-0805(2012-METRIC)_"))
    )
    (comp (ref "R39")
      (value "R-US_CHIP-0805(2012-METRIC)")
      (footprint "eagle-import:RESC2012X65")
      (libsource (lib "eagle-import") (part "R-USCHIP-0805(2012-METRIC)_"))
    )
    (comp (ref "R40")
      (value "R-US_CHIP-0805(2012-METRIC)")
      (footprint "eagle-import:RESC2012X65")
      (libsource (lib "eagle-import") (part "R-USCHIP-0805(2012-METRIC)_"))
    )
    (comp (ref "R41")
      (value "R-US_CHIP-0805(2012-METRIC)")
      (footprint "eagle-import:RESC2012X65")
      (libsource (lib "eagle-import") (part "R-USCHIP-0805(2012-METRIC)_"))
    )
    (comp (ref "R42")
      (value "R-US_CHIP-0805(2012-METRIC)")
      (footprint "eagle-import:RESC2012X65")
      (libsource (lib "eagle-import") (part "R-USCHIP-0805(2012-METRIC)_"))
    )
    (comp (ref "R43")
      (value "R-US_CHIP-0805(2012-METRIC)")
      (footprint "eagle-import:RESC2012X65")
      (libsource (lib "eagle-import") (part "R-USCHIP-0805(2012-METRIC)_"))
    )
    (comp (ref "R44")
      (value "R-US_CHIP-0805(2012-METRIC)")
      (footprint "eagle-import:RESC2012X65")
      (libsource (lib "eagle-import") (part "R-USCHIP-0805(2012-METRIC)_"))
    )
    (comp (ref "R45")
      (value "R-US_CHIP-0805(2012-METRIC)")
      (footprint "eagle-import:RESC2012X65")
      (libsource (lib "eagle-import") (part "R-USCHIP-0805(2012-METRIC)_"))
    )
    (comp (ref "R46")
      (value "R-US_CHIP-0805(2012-METRIC)")
      (footprint "eagle-import:RESC2012X65")
      (libsource (lib "eagle-import") (part "R-USCHIP-0805(2012-METRIC)_"))
    )
    (comp (ref "R47")
      (value "1k")
      (footprint "eagle-import:RESC1005X40")
      (fields (field (name "LCSC_PART") "C11702"))
      (libsource (lib "eagle-import") (part "Resistor_16378527_R-USCHIP-0402(1005-METRIC)_"))
    )
    (comp (ref "R48")
      (value "10k")
      (footprint "eagle-import:RESC1005X40")
      (fields (field (name "LCSC_PART") "C60490"))
      (libsource (lib "eagle-import") (part "Resistor_16378527_R-USCHIP-0402(1005-METRIC)_"))
    )
    (comp (ref "R49")
      (value "33")
      (footprint "eagle-import:RESC1005X40")
      (fields (field (name "LCSC_PART") "C25105"))
      (libsource (lib "eagle-import") (part "Resistor_16378527_R-USCHIP-0402(1005-METRIC)_"))
    )
    (comp (ref "R50")
      (value "33")
      (footprint "eagle-import:RESC1005X40")
      (fields (field (name "LCSC_PART") "C25105"))
      (libsource (lib "eagle-import") (part "Resistor_16378527_R-USCHIP-0402(1005-METRIC)_"))
    )
    (comp (ref "R51")
      (value "R-US_CHIP-0805(2012-METRIC)")
      (footprint "eagle-import:RESC2012X65")
      (libsource (lib "eagle-import") (part "R-USCHIP-0805(2012-METRIC)_"))
    )
    (comp (ref "R52")
      (value "R-US_CHIP-0805(2012-METRIC)")
      (footprint "eagle-import:RESC2012X65")
      (libsource (lib "eagle-import") (part "R-USCHIP-0805(2012-METRIC)_"))
    )
    (comp (ref "R53")
      (value "R-US_CHIP-0805(2012-METRIC)")
      (footprint "eagle-import:RESC2012X65")
      (libsource (lib "eagle-import") (part "R-USCHIP-0805(2012-METRIC)_"))
    )
    (comp (ref "R54")
      (value "R-US_CHIP-0805(2012-METRIC)")
      (footprint "eagle-import:RESC2012X65")
      (libsource (lib "eagle-import") (part "R-USCHIP-0805(2012-METRIC)_"))
    )
    (comp (ref "R55")
      (value "33")
      (footprint "eagle-import:RESC1005X40")
      (fields (field (name "LCSC_PART") "C25105"))
      (libsource (lib "eagle-import") (part "Resistor_16378527_R-USCHIP-0402(1005-METRIC)_"))
    )
    (comp (ref "R56")
      (value "R-US_CHIP-0805(2012-METRIC)")
      (footprint "eagle-import:RESC2012X65")
      (libsource (lib "eagle-import") (part "R-USCHIP-0805(2012-METRIC)_"))
    )
    (comp (ref "R57")
      (value "R-US_CHIP-0805(2012-METRIC)")
      (footprint "eagle-import:RESC2012X65")
      (libsource (lib "eagle-import") (part "R-USCHIP-0805(2012-METRIC)_"))
    )
    (comp (ref "R58")
      (value "R-US_CHIP-0805(2012-METRIC)")
      (footprint "eagle-import:RESC2012X65")
      (libsource (lib "eagle-import") (part "R-USCHIP-0805(2012-METRIC)_"))
    )
    (comp (ref "R59")
      (value "R-US_CHIP-0805(2012-METRIC)")
      (footprint "eagle-import:RESC2012X65")
      (libsource (lib "eagle-import") (part "R-USCHIP-0805(2012-METRIC)_"))
    )
    (comp (ref "R60")
      (value "R-US_CHIP-0805(2012-METRIC)")
      (footprint "eagle-import:RESC2012X65")
      (libsource (lib "eagle-import") (part "R-USCHIP-0805(2012-METRIC)_"))
    )
    (comp (ref "R61")
      (value "R-US_CHIP-0805(2012-METRIC)")
      (footprint "eagle-import:RESC2012X65")
      (libsource (lib "eagle-import") (part "R-USCHIP-0805(2012-METRIC)_"))
    )
    (comp (ref "R62")
      (value "R-US_CHIP-0805(2012-METRIC)")
      (footprint "eagle-import:RESC2012X65")
      (libsource (lib "eagle-import") (part "R-USCHIP-0805(2012-METRIC)_"))
    )
    (comp (ref "R63")
      (value "R-US_CHIP-0805(2012-METRIC)")
      (footprint "eagle-import:RESC2012X65")
      (libsource (lib "eagle-import") (part "R-USCHIP-0805(2012-METRIC)_"))
    )
    (comp (ref "R64")
      (value "R-US_CHIP-0805(2012-METRIC)")
      (footprint "eagle-import:RESC2012X65")
      (libsource (lib "eagle-import") (part "R-USCHIP-0805(2012-METRIC)_"))
    )
    (comp (ref "R65")
      (value "R-US_CHIP-0805(2012-METRIC)")
      (footprint "eagle-import:RESC2012X65")
      (libsource (lib "eagle-import") (part "R-USCHIP-0805(2012-METRIC)_"))
    )
    (comp (ref "R66")
      (value "R-US_CHIP-0805(2012-METRIC)")
      (footprint "eagle-import:RESC2012X65")
      (libsource (lib "eagle-import") (part "R-USCHIP-0805(2012-METRIC)_"))
    )
    (comp (ref "R67")
      (value "10k")
      (footprint "eagle-import:RESC2012X65")
      (fields (field (name "LCSC_PART") "C60490"))
      (libsource (lib "eagle-import") (part "Resistor_16378527_R-USCHIP-0805(2012-METRIC)_"))
    )
    (comp (ref "R68")
      (value "10k")
      (footprint "eagle-import:RESC2012X65")
      (fields (field (name "LCSC_PART") "C60490"))
      (libsource (lib "eagle-import") (part "Resistor_16378527_R-USCHIP-0805(2012-METRIC)_"))
    )
    (comp (ref "R69")
      (value "R-US_CHIP-0805(2012-METRIC)")
      (footprint "eagle-import:RESC2012X65")
      (libsource (lib "eagle-import") (part "R-USCHIP-0805(2012-METRIC)_"))
    )
    (comp (ref "R70")
      (value "R-US_CHIP-0805(2012-METRIC)")
      (footprint "eagle-import:RESC2012X65")
      (libsource (lib "eagle-import") (part "R-USCHIP-0805(2012-METRIC)_"))
    )
    (comp (ref "R71")
      (value "R-US_CHIP-0805(2012-METRIC)")
      (footprint "eagle-import:RESC2012X65")
      (libsource (lib "eagle-import") (part "R-USCHIP-0805(2012-METRIC)_"))
    )
    (comp (ref "R72")
      (value "R-US_CHIP-0805(2012-METRIC)")
      (footprint "eagle-import:RESC2012X65")
      (libsource (lib "eagle-import") (part "R-USCHIP-0805(2012-METRIC)_"))
    )
    (comp (ref "R73")
      (value "10k")
      (footprint "eagle-import:RESC2012X65")
      (fields (field (name "LCSC_PART") "C60490"))
      (libsource (lib "eagle-import") (part "Resistor_16378527_R-USCHIP-0805(2012-METRIC)_"))
    )
    (comp (ref "R74")
      (value "10k")
      (footprint "eagle-import:RESC2012X65")
      (fields (field (name "LCSC_PART") "C60490"))
      (libsource (lib "eagle-import") (part "Resistor_16378527_R-USCHIP-0805(2012-METRIC)_"))
    )
    (comp (ref "R75")
      (value "R-US_CHIP-0805(2012-METRIC)")
      (footprint "eagle-import:RESC2012X65")
      (libsource (lib "eagle-import") (part "R-USCHIP-0805(2012-METRIC)_"))
    )
    (comp (ref "R76")
      (value "R-US_CHIP-0805(2012-METRIC)")
      (footprint "eagle-import:RESC2012X65")
      (libsource (lib "eagle-import") (part "R-USCHIP-0805(2012-METRIC)_"))
    )
    (comp (ref "R77")
      (value "R-US_CHIP-0805(2012-METRIC)")
      (footprint "eagle-import:RESC2012X65")
      (libsource (lib "eagle-import") (part "R-USCHIP-0805(2012-METRIC)_"))
    )
    (comp (ref "R78")
      (value "R-US_CHIP-0805(2012-METRIC)")
      (footprint "eagle-import:RESC2012X65")
      (libsource (lib "eagle-import") (part "R-USCHIP-0805(2012-METRIC)_"))
    )
    (comp (ref "R79")
      (value "R-US_CHIP-0805(2012-METRIC)")
      (footprint "eagle-import:RESC2012X65")
      (libsource (lib "eagle-import") (part "R-USCHIP-0805(2012-METRIC)_"))
    )
    (comp (ref "R80")
      (value "R-US_CHIP-0805(2012-METRIC)")
      (footprint "eagle-import:RESC2012X65")
      (libsource (lib "eagle-import") (part "R-USCHIP-0805(2012-METRIC)_"))
    )
    (comp (ref "R81")
      (value "R-US_CHIP-0805(2012-METRIC)")
      (footprint "eagle-import:RESC2012X65")
      (libsource (lib "eagle-import") (part "R-USCHIP-0805(2012-METRIC)_"))
    )
    (comp (ref "R82")
      (value "R-US_CHIP-0805(2012-METRIC)")
      (footprint "eagle-import:RESC2012X65")
      (libsource (lib "eagle-import") (part "R-USCHIP-0805(2012-METRIC)_"))
    )
    (comp (ref "R83")
      (value "10k")
      (footprint "eagle-import:RESC2012X65")
      (fields (field (name "LCSC_PART") "C60490"))
      (libsource (lib "eagle-import") (part "Resistor_16378527_R-USCHIP-0805(2012-METRIC)_"))
    )
    (comp (ref "R84")
      (value "33")
      (footprint "eagle-import:RESC1005X40")
      (fields (field (name "LCSC_PART") "C25105"))
      (libsource (lib "eagle-import") (part "Resistor_16378527_R-USCHIP-0402(1005-METRIC)_"))
    )
    (comp (ref "R85")
      (value "R-US_CHIP-0805(2012-METRIC)")
      (footprint "eagle-import:RESC2012X65")
      (libsource (lib "eagle-import") (part "R-USCHIP-0805(2012-METRIC)_"))
    )
    (comp (ref "R86")
      (value "R-US_CHIP-0805(2012-METRIC)")
      (footprint "eagle-import:RESC2012X65")
      (libsource (lib "eagle-import") (part "R-USCHIP-0805(2012-METRIC)_"))
    )
    (comp (ref "R87")
      (value "R-US_CHIP-0805(2012-METRIC)")
      (footprint "eagle-import:RESC2012X65")
      (libsource (lib "eagle-import") (part "R-USCHIP-0805(2012-METRIC)_"))
    )
    (comp (ref "R88")
      (value "R-US_CHIP-0805(2012-METRIC)")
      (footprint "eagle-import:RESC2012X65")
      (libsource (lib "eagle-import") (part "R-USCHIP-0805(2012-METRIC)_"))
    )
    (comp (ref "R89")
      (value "R-US_CHIP-0805(2012-METRIC)")
      (footprint "eagle-import:RESC2012X65")
      (libsource (lib "eagle-import") (part "R-USCHIP-0805(2012-METRIC)_"))
    )
    (comp (ref "R90")
      (value "R-US_CHIP-0805(2012-METRIC)")
      (footprint "eagle-import:RESC2012X65")
      (libsource (lib "eagle-import") (part "R-USCHIP-0805(2012-METRIC)_"))
    )
    (comp (ref "R91")
      (value "R-US_CHIP-0805(2012-METRIC)")
      (footprint "eagle-import:RESC2012X65")
      (libsource (lib "eagle-import") (part "R-USCHIP-0805(2012-METRIC)_"))
    )
    (comp (ref "R92")
      (value "R-US_CHIP-0805(2012-METRIC)")
      (footprint "eagle-import:RESC2012X65")
      (libsource (lib "eagle-import") (part "R-USCHIP-0805(2012-METRIC)_"))
    )
    (comp (ref "R93")
      (value "10k")
      (footprint "eagle-import:RESC2012X65")
      (fields (field (name "LCSC_PART") "C60490"))
      (libsource (lib "eagle-import") (part "Resistor_16378527_R-USCHIP-0805(2012-METRIC)_"))
    )
    (comp (ref "R96")
      (value "5.1k")
      (footprint "eagle-import:RESC1005X40")
      (fields (field (name "LCSC_PART") "C25905"))
      (libsource (lib "eagle-import") (part "Resistor_16378527_R-USCHIP-0402(1005-METRIC)_"))
    )
    (comp (ref "R97")
      (value "5.1k")
      (footprint "eagle-import:RESC1005X40")
      (fields (field (name "LCSC_PART") "C25905"))
      (libsource (lib "eagle-import") (part "Resistor_16378527_R-USCHIP-0402(1005-METRIC)_"))
    )
    (comp (ref "R98")
      (value "10k")
      (footprint "eagle-import:RESC1005X40")
      (fields (field (name "LCSC_PART") "C60490"))
      (libsource (lib "eagle-import") (part "Resistor_16378527_R-USCHIP-0402(1005-METRIC)_"))
    )
    (comp (ref "R99")
      (value "10k")
      (footprint "eagle-import:RESC1005X40")
      (fields (field (name "LCSC_PART") "C60490"))
      (libsource (lib "eagle-import") (part "Resistor_16378527_R-USCHIP-0402(1005-METRIC)_"))
    )
    (comp (ref "TP20")
      (value "TPSB1,27")
      (footprint "eagle-import:B1,27")
      (libsource (lib "eagle-import") (part "TPSB1,27"))
    )
    (comp (ref "TP21")
      (value "TPSB1,27")
      (footprint "eagle-import:B1,27")
      (libsource (lib "eagle-import") (part "TPSB1,27"))
    )
    (comp (ref "TP22")
      (value "TPSB1,27")
      (footprint "eagle-import:B1,27")
      (libsource (lib "eagle-import") (part "TPSB1,27"))
    )
    (comp (ref "U$1")
      (value "PCB-ANTENNA")
      (footprint "eagle-import:PCB-ANTENNA")
      (libsource (lib "eagle-import") (part "PCB-ANTENNA"))
    )
    (comp (ref "U$2")
      (value "ACO97")
      (footprint "eagle-import:ACO97")
      (libsource (lib "eagle-import") (part "ACO97"))
    )
    (comp (ref "U1")
      (value "ESP32")
      (footprint "eagle-import:QFN56_ESP32-S2FH4_EXP-M")
      (libsource (lib "eagle-import") (part "ESP32"))
    )
    (comp (ref "U2")
      (value "ICE40")
      (footprint "eagle-import:ICE40-QFN")
      (libsource (lib "eagle-import") (part "ICE40"))
    )
    (comp (ref "U3")
      (value "NCV8161ASN330T1G")
      (footprint "eagle-import:TSOP5_3X1P5_ONS-M")
      (libsource (lib "eagle-import") (part "NCV8161ASN330T1G"))
    )
    (comp (ref "U4")
      (value "TPS76912DBVR")
      (footprint "eagle-import:TPS76912DBVR")
      (libsource (lib "eagle-import") (part "TPS76912DBVR"))
    )
    (comp (ref "U5")
      (value "CRYSTAL-OSC")
      (footprint "eagle-import:XTAL_ECS-400-10-36-CKY-TR")
      (libsource (lib "eagle-import") (part "CRYSTAL-OSC"))
    )
    (comp (ref "U6")
      (value "NCV8161ASN330T1G")
      (footprint "eagle-import:TSOP5_3X1P5_ONS-M")
      (libsource (lib "eagle-import") (part "NCV8161ASN330T1G"))
    )
    (comp (ref "U7")
      (value "TXB0101DBVR")
      (footprint "eagle-import:SOT95P280X145-6N")
      (fields (field (name "SPICEPREFIX") "X"))
      (libsource (lib "eagle-import") (part "TXB0101DBVR"))
    )
    (comp (ref "U9")
      (value "RGBLED")
      (footprint "eagle-import:RGBLED")
      (libsource (lib "eagle-import") (part "RGBLED"))
    )
    (comp (ref "U10")
      (value "TS-1185-C-A-A-A")
      (footprint "eagle-import:SW_CS1213AGF260_CRS")
      (libsource (lib "eagle-import") (part "TS-1185-C-A-A-A"))
    )
    (comp (ref "U11")
      (value "MAX-M10S-00B")
      (footprint "eagle-import:MAX-M10S-00B")
      (libsource (lib "eagle-import") (part "MAX-M10S-00B"))
    )
  )
  (nets
    (net (code "1") (name "+3.3V") (class "Default")
      (node (ref "C17") (pin "1") (pinfunction "1_1") (pintype "passive"))
      (node (ref "C18") (pin "1") (pinfunction "1_1") (pintype "passive"))
      (node (ref "C27") (pin "1") (pinfunction "1_1") (pintype "passive"))
      (node (ref "C33") (pin "1") (pinfunction "1_1") (pintype "passive"))
      (node (ref "C37") (pin "1") (pinfunction "1_1") (pintype "passive"))
      (node (ref "C38") (pin "1") (pinfunction "1_1") (pintype "passive"))
      (node (ref "C39") (pin "1") (pinfunction "1_1") (pintype "passive"))
      (node (ref "C40") (pin "1") (pinfunction "1_1") (pintype "passive"))
      (node (ref "C41") (pin "1") (pinfunction "1_1") (pintype "passive"))
      (node (ref "C42") (pin "1") (pinfunction "1_1") (pintype "passive"))
      (node (ref "C46") (pin "1") (pinfunction "1_1") (pintype "passive"))
      (node (ref "C48") (pin "1") (pinfunction "1_1") (pintype "passive"))
      (node (ref "C52") (pin "1") (pinfunction "1_1") (pintype "passive"))
      (node (ref "D3") (pin "2") (pinfunction "A_2") (pintype "passive"))
      (node (ref "L1") (pin "1") (pinfunction "1_1") (pintype "passive"))
      (node (ref "R20") (pin "2") (pinfunction "2_2") (pintype "passive"))
      (node (ref "R22") (pin "2") (pinfunction "2_2") (pintype "passive"))
      (node (ref "R23") (pin "1") (pinfunction "1_1") (pintype "passive"))
      (node (ref "R29") (pin "2") (pinfunction "2_2") (pintype "passive"))
      (node (ref "R98") (pin "1") (pinfunction "1_1") (pintype "passive"))
      (node (ref "TP21") (pin "TP") (pinfunction "PP_TP") (pintype "input"))
      (node (ref "U1") (pin "1") (pinfunction "VDDA_1") (pintype "passive"))
      (node (ref "U1") (pin "20") (pinfunction "VDD3P3_RTC_20") (pintype "passive"))
      (node (ref "U1") (pin "27") (pinfunction "VDD3P3_RTC_IO_27") (pintype "passive"))
      (node (ref "U1") (pin "30") (pinfunction "VDD_SPI_30") (pintype "passive"))
      (node (ref "U1") (pin "45") (pinfunction "VDD3P3_CPU_45") (pintype "passive"))
      (node (ref "U1") (pin "51") (pinfunction "VDDA_2_51") (pintype "passive"))
      (node (ref "U1") (pin "54") (pinfunction "VDDA_3_54") (pintype "passive"))
      (node (ref "U11") (pin "P$7") (pinfunction "V_IO_P$7") (pintype "bidirectional"))
      (node (ref "U11") (pin "P$8") (pinfunction "VCC_P$8") (pintype "bidirectional"))
      (node (ref "U2") (pin "1") (pinfunction "VCCIO_1_1") (pintype "power_in"))
      (node (ref "U2") (pin "22") (pinfunction "SPI_VCCIO1_22") (pintype "power_in"))
      (node (ref "U2") (pin "24") (pinfunction "VPP_2V5_24") (pintype "power_in"))
      (node (ref "U2") (pin "33") (pinfunction "VCCIO_0_33") (pintype "power_in"))
      (node (ref "U3") (pin "5") (pinfunction "OUT_5") (pintype "output"))
      (node (ref "U4") (pin "1") (pinfunction "IN_1") (pintype "input"))
      (node (ref "U7") (pin "1") (pinfunction "VCCA_1") (pintype "power_in"))
      (node (ref "U9") (pin "P$1") (pinfunction "P$1_P$1") (pintype "bidirectional"))
    )
    (net (code "2") (name "+5V") (class "Default")
      (node (ref "C10") (pin "1") (pinfunction "1_1") (pintype "passive"))
      (node (ref "C11") (pin "1") (pinfunction "1_1") (pintype "passive"))
      (node (ref "C12") (pin "1") (pinfunction "1_1") (pintype "passive"))
      (node (ref "C13") (pin "1") (pinfunction "1_1") (pintype "passive"))
      (node (ref "C14") (pin "1") (pinfunction "1_1") (pintype "passive"))
      (node (ref "C16") (pin "1") (pinfunction "1_1") (pintype "passive"))
      (node (ref "C3") (pin "1") (pinfunction "1_1") (pintype "passive"))
      (node (ref "C4") (pin "1") (pinfunction "1_1") (pintype "passive"))
      (node (ref "C5") (pin "1") (pinfunction "1_1") (pintype "passive"))
      (node (ref "C8") (pin "1") (pinfunction "1_1") (pintype "passive"))
      (node (ref "C9") (pin "1") (pinfunction "1_1") (pintype "passive"))
      (node (ref "J1") (pin "A4/B9") (pinfunction "VBUS_A4/B9") (pintype "power_in"))
      (node (ref "J1") (pin "B4/A9") (pinfunction "VBUS_B4/A9") (pintype "power_in"))
      (node (ref "R15") (pin "2") (pinfunction "2_2") (pintype "passive"))
      (node (ref "R16") (pin "2") (pinfunction "2_2") (pintype "passive"))
      (node (ref "R17") (pin "2") (pinfunction "2_2") (pintype "passive"))
      (node (ref "R18") (pin "2") (pinfunction "2_2") (pintype "passive"))
      (node (ref "R2") (pin "2") (pinfunction "2_2") (pintype "passive"))
      (node (ref "R24") (pin "2") (pinfunction "2_2") (pintype "passive"))
      (node (ref "R25") (pin "2") (pinfunction "2_2") (pintype "passive"))
      (node (ref "R26") (pin "2") (pinfunction "2_2") (pintype "passive"))
      (node (ref "R27") (pin "2") (pinfunction "2_2") (pintype "passive"))
      (node (ref "R30") (pin "2") (pinfunction "2_2") (pintype "passive"))
      (node (ref "R31") (pin "2") (pinfunction "2_2") (pintype "passive"))
      (node (ref "R32") (pin "2") (pinfunction "2_2") (pintype "passive"))
      (node (ref "R33") (pin "2") (pinfunction "2_2") (pintype "passive"))
      (node (ref "R34") (pin "2") (pinfunction "2_2") (pintype "passive"))
      (node (ref "R35") (pin "2") (pinfunction "2_2") (pintype "passive"))
      (node (ref "R36") (pin "2") (pinfunction "2_2") (pintype "passive"))
      (node (ref "R37") (pin "2") (pinfunction "2_2") (pintype "passive"))
      (node (ref "R38") (pin "2") (pinfunction "2_2") (pintype "passive"))
      (node (ref "R39") (pin "2") (pinfunction "2_2") (pintype "passive"))
      (node (ref "R40") (pin "2") (pinfunction "2_2") (pintype "passive"))
      (node (ref "R41") (pin "2") (pinfunction "2_2") (pintype "passive"))
      (node (ref "R42") (pin "2") (pinfunction "2_2") (pintype "passive"))
      (node (ref "R43") (pin "2") (pinfunction "2_2") (pintype "passive"))
      (node (ref "R44") (pin "2") (pinfunction "2_2") (pintype "passive"))
      (node (ref "R45") (pin "2") (pinfunction "2_2") (pintype "passive"))
      (node (ref "R51") (pin "2") (pinfunction "2_2") (pintype "passive"))
      (node (ref "R52") (pin "2") (pinfunction "2_2") (pintype "passive"))
      (node (ref "R53") (pin "2") (pinfunction "2_2") (pintype "passive"))
      (node (ref "R54") (pin "2") (pinfunction "2_2") (pintype "passive"))
      (node (ref "R56") (pin "2") (pinfunction "2_2") (pintype "passive"))
      (node (ref "R57") (pin "2") (pinfunction "2_2") (pintype "passive"))
      (node (ref "R58") (pin "2") (pinfunction "2_2") (pintype "passive"))
      (node (ref "R59") (pin "2") (pinfunction "2_2") (pintype "passive"))
      (node (ref "R6") (pin "2") (pinfunction "2_2") (pintype "passive"))
      (node (ref "R60") (pin "2") (pinfunction "2_2") (pintype "passive"))
      (node (ref "R61") (pin "2") (pinfunction "2_2") (pintype "passive"))
      (node (ref "R62") (pin "2") (pinfunction "2_2") (pintype "passive"))
      (node (ref "R63") (pin "2") (pinfunction "2_2") (pintype "passive"))
      (node (ref "R64") (pin "2") (pinfunction "2_2") (pintype "passive"))
      (node (ref "R65") (pin "2") (pinfunction "2_2") (pintype "passive"))
      (node (ref "R66") (pin "2") (pinfunction "2_2") (pintype "passive"))
      (node (ref "R69") (pin "2") (pinfunction "2_2") (pintype "passive"))
      (node (ref "R7") (pin "2") (pinfunction "2_2") (pintype "passive"))
      (node (ref "R70") (pin "2") (pinfunction "2_2") (pintype "passive"))
      (node (ref "R71") (pin "2") (pinfunction "2_2") (pintype "passive"))
      (node (ref "R72") (pin "2") (pinfunction "2_2") (pintype "passive"))
      (node (ref "R75") (pin "2") (pinfunction "2_2") (pintype "passive"))
      (node (ref "R76") (pin "2") (pinfunction "2_2") (pintype "passive"))
      (node (ref "R77") (pin "2") (pinfunction "2_2") (pintype "passive"))
      (node (ref "R78") (pin "2") (pinfunction "2_2") (pintype "passive"))
      (node (ref "R79") (pin "2") (pinfunction "2_2") (pintype "passive"))
      (node (ref "R8") (pin "2") (pinfunction "2_2") (pintype "passive"))
      (node (ref "R80") (pin "2") (pinfunction "2_2") (pintype "passive"))
      (node (ref "R81") (pin "2") (pinfunction "2_2") (pintype "passive"))
      (node (ref "R82") (pin "2") (pinfunction "2_2") (pintype "passive"))
      (node (ref "R85") (pin "2") (pinfunction "2_2") (pintype "passive"))
      (node (ref "R86") (pin "2") (pinfunction "2_2") (pintype "passive"))
      (node (ref "R87") (pin "2") (pinfunction "2_2") (pintype "passive"))
      (node (ref "R88") (pin "2") (pinfunction "2_2") (pintype "passive"))
      (node (ref "R89") (pin "2") (pinfunction "2_2") (pintype "passive"))
      (node (ref "R9") (pin "2") (pinfunction "2_2") (pintype "passive"))
      (node (ref "R90") (pin "2") (pinfunction "2_2") (pintype "passive"))
      (node (ref "R91") (pin "2") (pinfunction "2_2") (pintype "passive"))
      (node (ref "R92") (pin "2") (pinfunction "2_2") (pintype "passive"))
      (node (ref "TP20") (pin "TP") (pinfunction "PP_TP") (pintype "input"))
      (node (ref "U3") (pin "1") (pinfunction "IN_1") (pintype "passive"))
      (node (ref "U3") (pin "3") (pinfunction "EN_3") (pintype "passive"))
      (node (ref "U6") (pin "1") (pinfunction "IN_1") (pintype "passive"))
      (node (ref "U7") (pin "6") (pinfunction "VCCB_6") (pintype "power_in"))
    )
    (net (code "3") (name "/+1.2V") (class "Default")
      (node (ref "C45") (pin "1") (pinfunction "1_1") (pintype "passive"))
      (node (ref "C49") (pin "1") (pinfunction "1_1") (pintype "passive"))
      (node (ref "C50") (pin "1") (pinfunction "1_1") (pintype "passive"))
      (node (ref "L2") (pin "1") (pinfunction "1_1") (pintype "passive"))
      (node (ref "TP22") (pin "TP") (pinfunction "PP_TP") (pintype "input"))
      (node (ref "U2") (pin "30") (pinfunction "VCC_2_30") (pintype "power_in"))
      (node (ref "U2") (pin "5") (pinfunction "VCC_1_5") (pintype "power_in"))
      (node (ref "U4") (pin "5") (pinfunction "OUT_5") (pintype "output"))
    )
    (net (code "4") (name "/+1.2V_PLL") (class "Default")
      (node (ref "C43") (pin "1") (pinfunction "1_1") (pintype "passive"))
      (node (ref "C44") (pin "1") (pinfunction "1_1") (pintype "passive"))
      (node (ref "L2") (pin "2") (pinfunction "2_2") (pintype "passive"))
      (node (ref "U2") (pin "29") (pinfunction "VCCPLL_29") (pintype "power_in"))
    )
    (net (code "5") (name "/ANTENNA") (class "Default")
      (node (ref "C2") (pin "1") (pinfunction "1_1") (pintype "passive"))
      (node (ref "L3") (pin "2") (pinfunction "2_2") (pintype "passive"))
      (node (ref "U$1") (pin "P$2") (pinfunction "P$2_P$2") (pintype "bidirectional"))
    )
    (net (code "6") (name "/BIT0") (class "Default")
      (node (ref "Q1") (pin "1") (pinfunction "G_1") (pintype "passive"))
      (node (ref "R1") (pin "2") (pinfunction "2_2") (pintype "passive"))
      (node (ref "U2") (pin "48") (pinfunction "IOB_4A_48") (pintype "bidirectional"))
    )
    (net (code "7") (name "/BIT1") (class "Default")
      (node (ref "Q2") (pin "1") (pinfunction "G_1") (pintype "passive"))
      (node (ref "R12") (pin "2") (pinfunction "2_2") (pintype "passive"))
      (node (ref "U2") (pin "47") (pinfunction "IOB_2A_47") (pintype "bidirectional"))
    )
    (net (code "8") (name "/BIT2") (class "Default")
      (node (ref "Q3") (pin "1") (pinfunction "G_1") (pintype "passive"))
      (node (ref "R21") (pin "1") (pinfunction "1_1") (pintype "passive"))
      (node (ref "U2") (pin "46") (pinfunction "IOB_0A_46") (pintype "bidirectional"))
    )
    (net (code "9") (name "/BIT3") (class "Default")
      (node (ref "Q4") (pin "1") (pinfunction "G_1") (pintype "passive"))
      (node (ref "R4") (pin "1") (pinfunction "1_1") (pintype "passive"))
      (node (ref "U2") (pin "45") (pinfunction "IOB_5B_45") (pintype "bidirectional"))
    )
    (net (code "10") (name "/BIT4") (class "Default")
      (node (ref "Q5") (pin "1") (pinfunction "G_1") (pintype "passive"))
      (node (ref "R5") (pin "1") (pinfunction "1_1") (pintype "passive"))
      (node (ref "U2") (pin "43") (pinfunction "IOT_49A_43") (pintype "bidirectional"))
    )
    (net (code "11") (name "/BIT5") (class "Default")
      (node (ref "Q6") (pin "1") (pinfunction "G_1") (pintype "passive"))
      (node (ref "R10") (pin "1") (pinfunction "1_1") (pintype "passive"))
      (node (ref "U2") (pin "42") (pinfunction "IOT_51A_42") (pintype "bidirectional"))
    )
    (net (code "12") (name "/BIT6") (class "Default")
      (node (ref "Q7") (pin "1") (pinfunction "G_1") (pintype "passive"))
      (node (ref "R11") (pin "1") (pinfunction "1_1") (pintype "passive"))
      (node (ref "U2") (pin "38") (pinfunction "IOT_50B_38") (pintype "bidirectional"))
    )
    (net (code "13") (name "/BIT7") (class "Default")
      (node (ref "Q8") (pin "1") (pinfunction "G_1") (pintype "passive"))
      (node (ref "R13") (pin "1") (pinfunction "1_1") (pintype "passive"))
      (node (ref "U2") (pin "37") (pinfunction "IOT_45A_G1_37") (pintype "bidirectional"))
    )
    (net (code "14") (name "/BIT8") (class "Default")
      (node (ref "Q9") (pin "1") (pinfunction "G_1") (pintype "passive"))
      (node (ref "R14") (pin "1") (pinfunction "1_1") (pintype "passive"))
      (node (ref "U2") (pin "36") (pinfunction "IOT_48B_36") (pintype "bidirectional"))
    )
    (net (code "15") (name "/BIT9") (class "Default")
      (node (ref "Q10") (pin "1") (pinfunction "G_1") (pintype "passive"))
      (node (ref "R19") (pin "1") (pinfunction "1_1") (pintype "passive"))
      (node (ref "U2") (pin "35") (pinfunction "IOT_46B_G0_35") (pintype "bidirectional"))
    )
    (net (code "16") (name "/BIT10") (class "Default")
      (node (ref "Q11") (pin "1") (pinfunction "G_1") (pintype "passive"))
      (node (ref "R67") (pin "1") (pinfunction "1_1") (pintype "passive"))
      (node (ref "U2") (pin "34") (pinfunction "IOT_44B_34") (pintype "bidirectional"))
    )
    (net (code "17") (name "/BIT11") (class "Default")
      (node (ref "Q12") (pin "1") (pinfunction "G_1") (pintype "passive"))
      (node (ref "R68") (pin "1") (pinfunction "1_1") (pintype "passive"))
      (node (ref "U2") (pin "32") (pinfunction "IOT_43A_32") (pintype "bidirectional"))
    )
    (net (code "18") (name "/BIT12") (class "Default")
      (node (ref "Q13") (pin "1") (pinfunction "G_1") (pintype "passive"))
      (node (ref "R73") (pin "1") (pinfunction "1_1") (pintype "passive"))
      (node (ref "U2") (pin "31") (pinfunction "IOT_42B_31") (pintype "bidirectional"))
    )
    (net (code "19") (name "/BIT13") (class "Default")
      (node (ref "Q14") (pin "1") (pinfunction "G_1") (pintype "passive"))
      (node (ref "R74") (pin "1") (pinfunction "1_1") (pintype "passive"))
      (node (ref "U2") (pin "28") (pinfunction "IOT_41A_28") (pintype "bidirectional"))
    )
    (net (code "20") (name "/BIT14") (class "Default")
      (node (ref "Q15") (pin "1") (pinfunction "G_1") (pintype "passive"))
      (node (ref "R83") (pin "1") (pinfunction "1_1") (pintype "passive"))
      (node (ref "U2") (pin "27") (pinfunction "IOT_38B_27") (pintype "bidirectional"))
    )
    (net (code "21") (name "/BIT15") (class "Default")
      (node (ref "Q16") (pin "1") (pinfunction "G_1") (pintype "passive"))
      (node (ref "R93") (pin "1") (pinfunction "1_1") (pintype "passive"))
      (node (ref "U2") (pin "26") (pinfunction "IOT_39A_26") (pintype "bidirectional"))
    )
    (net (code "22") (name "/CDONE") (class "Default")
      (node (ref "R29") (pin "1") (pinfunction "1_1") (pintype "passive"))
      (node (ref "U1") (pin "41") (pinfunction "GPIO37_41") (pintype "passive"))
      (node (ref "U2") (pin "7") (pinfunction "CDONE_7") (pintype "bidirectional"))
    )
    (net (code "23") (name "/CHIP_PU") (class "Default")
      (node (ref "C32") (pin "1") (pinfunction "1_1") (pintype "passive"))
      (node (ref "R22") (pin "1") (pinfunction "1_1") (pintype "passive"))
      (node (ref "U1") (pin "56") (pinfunction "CHIP_PU_56") (pintype "passive"))
    )
    (net (code "24") (name "/CPU_LED") (class "Default")
      (node (ref "D1") (pin "C") (pinfunction "C_C") (pintype "passive"))
      (node (ref "U1") (pin "7") (pinfunction "GPIO2_7") (pintype "passive"))
    )
    (net (code "25") (name "/CRESET_B") (class "Default")
      (node (ref "R28") (pin "2") (pinfunction "2_2") (pintype "passive"))
      (node (ref "U1") (pin "40") (pinfunction "GPIO36_40") (pintype "passive"))
      (node (ref "U2") (pin "8") (pinfunction "CRESET_B_8") (pintype "passive"))
    )
    (net (code "26") (name "/ESP_31") (class "Default")
      (node (ref "U1") (pin "31") (pinfunction "SPIHD_31") (pintype "passive"))
    )
    (net (code "27") (name "/ESP_32") (class "Default")
      (node (ref "U1") (pin "32") (pinfunction "SPIWP_32") (pintype "passive"))
    )
    (net (code "28") (name "/ESP_33") (class "Default")
      (node (ref "U1") (pin "33") (pinfunction "SPICS0_33") (pintype "passive"))
    )
    (net (code "29") (name "/ESP_35") (class "Default")
      (node (ref "U1") (pin "35") (pinfunction "SPIQ_35") (pintype "passive"))
    )
    (net (code "30") (name "/ESP_36") (class "Default")
      (node (ref "U1") (pin "36") (pinfunction "SPID_36") (pintype "passive"))
    )
    (net (code "31") (name "/ESP_38") (class "Default")
      (node (ref "U1") (pin "38") (pinfunction "GPIO34_38") (pintype "passive"))
    )
    (net (code "32") (name "/ESP_39") (class "Default")
      (node (ref "U1") (pin "39") (pinfunction "GPIO35_39") (pintype "passive"))
    )
    (net (code "33") (name "/EXT_5") (class "Default")
      (node (ref "E2") (pin "SIG") (pinfunction "SIGNAL_SIG") (pintype "bidirectional"))
      (node (ref "U7") (pin "4") (pinfunction "B_4") (pintype "bidirectional"))
    )
    (net (code "34") (name "/EXT_33") (class "Default")
      (node (ref "U11") (pin "P$5") (pinfunction "EXTINT_P$5") (pintype "bidirectional"))
      (node (ref "U2") (pin "12") (pinfunction "IOB_22A_12") (pintype "bidirectional"))
      (node (ref "U7") (pin "3") (pinfunction "A_3") (pintype "bidirectional"))
    )
    (net (code "35") (name "/EXT_EN") (class "Default")
      (node (ref "R48") (pin "1") (pinfunction "1_1") (pintype "passive"))
      (node (ref "U2") (pin "11") (pinfunction "IOB_20A_11") (pintype "bidirectional"))
      (node (ref "U7") (pin "5") (pinfunction "OE_5") (pintype "input"))
    )
    (net (code "36") (name "/F2") (class "Default")
      (node (ref "U2") (pin "2") (pinfunction "IOB_6A_2") (pintype "bidirectional"))
    )
    (net (code "37") (name "/F3") (class "Default")
      (node (ref "U2") (pin "3") (pinfunction "IOB_9B_3") (pintype "bidirectional"))
    )
    (net (code "38") (name "/F4") (class "Default")
      (node (ref "U2") (pin "4") (pinfunction "IOB_8A_4") (pintype "bidirectional"))
    )
    (net (code "39") (name "/F6") (class "Default")
      (node (ref "U2") (pin "6") (pinfunction "IOB_13B_6") (pintype "bidirectional"))
    )
    (net (code "40") (name "/F9") (class "Default")
      (node (ref "U2") (pin "9") (pinfunction "IOB_16A_9") (pintype "bidirectional"))
    )
    (net (code "41") (name "/F10") (class "Default")
      (node (ref "U2") (pin "10") (pinfunction "IOB_18A_10") (pintype "bidirectional"))
    )
    (net (code "42") (name "/F19") (class "Default")
      (node (ref "U2") (pin "19") (pinfunction "IOB_29B_19") (pintype "bidirectional"))
    )
    (net (code "43") (name "/F20") (class "Default")
      (node (ref "U2") (pin "20") (pinfunction "IOB_25B_G3_20") (pintype "bidirectional"))
    )
    (net (code "44") (name "/F23") (class "Default")
      (node (ref "U2") (pin "23") (pinfunction "IOT_37A_23") (pintype "bidirectional"))
    )
    (net (code "45") (name "/F25") (class "Default")
      (node (ref "U2") (pin "25") (pinfunction "IOT_36B_25") (pintype "bidirectional"))
    )
    (net (code "46") (name "/FSPI_CLK") (class "Default")
      (node (ref "U1") (pin "17") (pinfunction "GPIO12/FSPI_CLK_17") (pintype "passive"))
      (node (ref "U2") (pin "15") (pinfunction "IOB_34A_SPI_SCK_15") (pintype "bidirectional"))
    )
    (net (code "47") (name "/FSPI_CS") (class "Default")
      (node (ref "U1") (pin "15") (pinfunction "GPIO10/FSPI_CSO_15") (pintype "passive"))
      (node (ref "U2") (pin "16") (pinfunction "IOB_35B_SPI_SS_16") (pintype "bidirectional"))
    )
    (net (code "48") (name "/FSPI_HD") (class "Default")
      (node (ref "U1") (pin "14") (pinfunction "GPIO9/FSPI_HD_14") (pintype "passive"))
      (node (ref "U2") (pin "18") (pinfunction "IOB_31B_18") (pintype "bidirectional"))
    )
    (net (code "49") (name "/FSPI_MISO") (class "Default")
      (node (ref "U1") (pin "18") (pinfunction "GPIO13/FPSPI_Q_18") (pintype "passive"))
      (node (ref "U2") (pin "14") (pinfunction "IOB_32A_SPI_SO_14") (pintype "bidirectional"))
    )
    (net (code "50") (name "/FSPI_MOSI") (class "Default")
      (node (ref "U1") (pin "16") (pinfunction "GPIO11/FSPI_D_16") (pintype "passive"))
      (node (ref "U2") (pin "17") (pinfunction "IOB_33B_SPI_SI_17") (pintype "bidirectional"))
    )
    (net (code "51") (name "/FSPI_WP") (class "Default")
      (node (ref "U1") (pin "19") (pinfunction "GPIO14/FSPI_WP_19") (pintype "passive"))
      (node (ref "U2") (pin "13") (pinfunction "IOB_24A_13") (pintype "bidirectional"))
    )
    (net (code "52") (name "/GPIO0") (class "Default")
      (node (ref "R20") (pin "1") (pinfunction "1_1") (pintype "passive"))
      (node (ref "U1") (pin "5") (pinfunction "GPIO0_5") (pintype "passive"))
      (node (ref "U10") (pin "2") (pinfunction "2_2") (pintype "passive"))
    )
    (net (code "53") (name "/GPS-BKUP") (class "Default")
      (node (ref "C20") (pin "1") (pinfunction "1_1") (pintype "passive"))
      (node (ref "R46") (pin "1") (pinfunction "1_1") (pintype "passive"))
      (node (ref "U11") (pin "P$6") (pinfunction "V_BCKP_P$6") (pintype "bidirectional"))
    )
    (net (code "54") (name "/GPS-PPS") (class "Default")
      (node (ref "R47") (pin "2") (pinfunction "2_2") (pintype "passive"))
      (node (ref "R50") (pin "1") (pinfunction "1_1") (pintype "passive"))
      (node (ref "U1") (pin "42") (pinfunction "GPIO38_42") (pintype "passive"))
      (node (ref "U2") (pin "44") (pinfunction "IOB_3B_G6_44") (pintype "bidirectional"))
    )
    (net (code "55") (name "/GPS-RX") (class "Default")
      (node (ref "R49") (pin "1") (pinfunction "1_1") (pintype "passive"))
      (node (ref "U1") (pin "48") (pinfunction "U0TXD_48") (pintype "passive"))
    )
    (net (code "56") (name "/GPS-TX") (class "Default")
      (node (ref "R55") (pin "1") (pinfunction "1_1") (pintype "passive"))
      (node (ref "U1") (pin "49") (pinfunction "U0RXD_49") (pintype "passive"))
    )
    (net (code "57") (name "/GPS_RESET") (class "Default")
      (node (ref "R98") (pin "2") (pinfunction "2_2") (pintype "passive"))
      (node (ref "U1") (pin "37") (pinfunction "GPIO33_37") (pintype "passive"))
      (node (ref "U11") (pin "P$9") (pinfunction "RESET_N_P$9") (pintype "bidirectional"))
    )
    (net (code "58") (name "/HQ_OSC") (class "Default")
      (node (ref "U$2") (pin "OUT") (pinfunction "OUT_OUT") (pintype "bidirectional"))
      (node (ref "U2") (pin "21") (pinfunction "IOB_23B_21") (pintype "bidirectional"))
    )
    (net (code "59") (name "/LED0") (class "Default")
      (node (ref "D4") (pin "C") (pinfunction "C_C") (pintype "passive"))
      (node (ref "D5") (pin "C") (pinfunction "C_C") (pintype "passive"))
      (node (ref "D6") (pin "C") (pinfunction "C_C") (pintype "passive"))
      (node (ref "D7") (pin "C") (pinfunction "C_C") (pintype "passive"))
      (node (ref "Q1") (pin "3") (pinfunction "D_3") (pintype "passive"))
    )
    (net (code "60") (name "/LED1") (class "Default")
      (node (ref "D12") (pin "C") (pinfunction "C_C") (pintype "passive"))
      (node (ref "D13") (pin "C") (pinfunction "C_C") (pintype "passive"))
      (node (ref "D14") (pin "C") (pinfunction "C_C") (pintype "passive"))
      (node (ref "D15") (pin "C") (pinfunction "C_C") (pintype "passive"))
      (node (ref "Q2") (pin "3") (pinfunction "D_3") (pintype "passive"))
    )
    (net (code "61") (name "/LED2") (class "Default")
      (node (ref "D20") (pin "C") (pinfunction "C_C") (pintype "passive"))
      (node (ref "D21") (pin "C") (pinfunction "C_C") (pintype "passive"))
      (node (ref "D22") (pin "C") (pinfunction "C_C") (pintype "passive"))
      (node (ref "D23") (pin "C") (pinfunction "C_C") (pintype "passive"))
      (node (ref "Q3") (pin "3") (pinfunction "D_3") (pintype "passive"))
    )
    (net (code "62") (name "/LED3") (class "Default")
      (node (ref "D28") (pin "C") (pinfunction "C_C") (pintype "passive"))
      (node (ref "D29") (pin "C") (pinfunction "C_C") (pintype "passive"))
      (node (ref "D30") (pin "C") (pinfunction "C_C") (pintype "passive"))
      (node (ref "D31") (pin "C") (pinfunction "C_C") (pintype "passive"))
      (node (ref "Q4") (pin "3") (pinfunction "D_3") (pintype "passive"))
    )
    (net (code "63") (name "/LED4") (class "Default")
      (node (ref "D36") (pin "C") (pinfunction "C_C") (pintype "passive"))
      (node (ref "D37") (pin "C") (pinfunction "C_C") (pintype "passive"))
      (node (ref "D38") (pin "C") (pinfunction "C_C") (pintype "passive"))
      (node (ref "D39") (pin "C") (pinfunction "C_C") (pintype "passive"))
      (node (ref "Q5") (pin "3") (pinfunction "D_3") (pintype "passive"))
    )
    (net (code "64") (name "/LED5") (class "Default")
      (node (ref "D44") (pin "C") (pinfunction "C_C") (pintype "passive"))
      (node (ref "D45") (pin "C") (pinfunction "C_C") (pintype "passive"))
      (node (ref "D46") (pin "C") (pinfunction "C_C") (pintype "passive"))
      (node (ref "D47") (pin "C") (pinfunction "C_C") (pintype "passive"))
      (node (ref "Q6") (pin "3") (pinfunction "D_3") (pintype "passive"))
    )
    (net (code "65") (name "/LED6") (class "Default")
      (node (ref "D52") (pin "C") (pinfunction "C_C") (pintype "passive"))
      (node (ref "D53") (pin "C") (pinfunction "C_C") (pintype "passive"))
      (node (ref "D54") (pin "C") (pinfunction "C_C") (pintype "passive"))
      (node (ref "D55") (pin "C") (pinfunction "C_C") (pintype "passive"))
      (node (ref "Q7") (pin "3") (pinfunction "D_3") (pintype "passive"))
    )
    (net (code "66") (name "/LED7") (class "Default")
      (node (ref "D60") (pin "C") (pinfunction "C_C") (pintype "passive"))
      (node (ref "D61") (pin "C") (pinfunction "C_C") (pintype "passive"))
      (node (ref "D62") (pin "C") (pinfunction "C_C") (pintype "passive"))
      (node (ref "D63") (pin "C") (pinfunction "C_C") (pintype "passive"))
      (node (ref "Q8") (pin "3") (pinfunction "D_3") (pintype "passive"))
    )
    (net (code "67") (name "/LED8") (class "Default")
      (node (ref "D68") (pin "C") (pinfunction "C_C") (pintype "passive"))
      (node (ref "D69") (pin "C") (pinfunction "C_C") (pintype "passive"))
      (node (ref "D70") (pin "C") (pinfunction "C_C") (pintype "passive"))
      (node (ref "D71") (pin "C") (pinfunction "C_C") (pintype "passive"))
      (node (ref "Q9") (pin "3") (pinfunction "D_3") (pintype "passive"))
    )
    (net (code "68") (name "/LED9") (class "Default")
      (node (ref "D76") (pin "C") (pinfunction "C_C") (pintype "passive"))
      (node (ref "D77") (pin "C") (pinfunction "C_C") (pintype "passive"))
      (node (ref "D78") (pin "C") (pinfunction "C_C") (pintype "passive"))
      (node (ref "D79") (pin "C") (pinfunction "C_C") (pintype "passive"))
      (node (ref "Q10") (pin "3") (pinfunction "D_3") (pintype "passive"))
    )
    (net (code "69") (name "/LED10") (class "Default")
      (node (ref "D10") (pin "C") (pinfunction "C_C") (pintype "passive"))
      (node (ref "D11") (pin "C") (pinfunction "C_C") (pintype "passive"))
      (node (ref "D2") (pin "C") (pinfunction "C_C") (pintype "passive"))
      (node (ref "D8") (pin "C") (pinfunction "C_C") (pintype "passive"))
      (node (ref "Q11") (pin "3") (pinfunction "D_3") (pintype "passive"))
    )
    (net (code "70") (name "/LED11") (class "Default")
      (node (ref "D16") (pin "C") (pinfunction "C_C") (pintype "passive"))
      (node (ref "D17") (pin "C") (pinfunction "C_C") (pintype "passive"))
      (node (ref "D18") (pin "C") (pinfunction "C_C") (pintype "passive"))
      (node (ref "D19") (pin "C") (pinfunction "C_C") (pintype "passive"))
      (node (ref "Q12") (pin "3") (pinfunction "D_3") (pintype "passive"))
    )
    (net (code "71") (name "/LED12") (class "Default")
      (node (ref "D24") (pin "C") (pinfunction "C_C") (pintype "passive"))
      (node (ref "D25") (pin "C") (pinfunction "C_C") (pintype "passive"))
      (node (ref "D26") (pin "C") (pinfunction "C_C") (pintype "passive"))
      (node (ref "D27") (pin "C") (pinfunction "C_C") (pintype "passive"))
      (node (ref "Q13") (pin "3") (pinfunction "D_3") (pintype "passive"))
    )
    (net (code "72") (name "/LED13") (class "Default")
      (node (ref "D32") (pin "C") (pinfunction "C_C") (pintype "passive"))
      (node (ref "D33") (pin "C") (pinfunction "C_C") (pintype "passive"))
      (node (ref "D34") (pin "C") (pinfunction "C_C") (pintype "passive"))
      (node (ref "D35") (pin "C") (pinfunction "C_C") (pintype "passive"))
      (node (ref "Q14") (pin "3") (pinfunction "D_3") (pintype "passive"))
    )
    (net (code "73") (name "/LED14") (class "Default")
      (node (ref "D40") (pin "C") (pinfunction "C_C") (pintype "passive"))
      (node (ref "D41") (pin "C") (pinfunction "C_C") (pintype "passive"))
      (node (ref "D42") (pin "C") (pinfunction "C_C") (pintype "passive"))
      (node (ref "D43") (pin "C") (pinfunction "C_C") (pintype "passive"))
      (node (ref "Q15") (pin "3") (pinfunction "D_3") (pintype "passive"))
    )
    (net (code "74") (name "/LED15") (class "Default")
      (node (ref "D48") (pin "C") (pinfunction "C_C") (pintype "passive"))
      (node (ref "D49") (pin "C") (pinfunction "C_C") (pintype "passive"))
      (node (ref "D50") (pin "C") (pinfunction "C_C") (pintype "passive"))
      (node (ref "D51") (pin "C") (pinfunction "C_C") (pintype "passive"))
      (node (ref "Q16") (pin "3") (pinfunction "D_3") (pintype "passive"))
    )
    (net (code "75") (name "/LNA_IN") (class "Default")
      (node (ref "C1") (pin "1") (pinfunction "1_1") (pintype "passive"))
      (node (ref "L3") (pin "1") (pinfunction "1_1") (pintype "passive"))
      (node (ref "U1") (pin "2") (pinfunction "LNA_IN_2") (pintype "passive"))
    )
    (net (code "76") (name "/OXCO_EN") (class "Default")
      (node (ref "R99") (pin "2") (pinfunction "2_2") (pintype "passive"))
      (node (ref "U1") (pin "34") (pinfunction "SPICLK_34") (pintype "passive"))
      (node (ref "U6") (pin "3") (pinfunction "EN_3") (pintype "passive"))
    )
    (net (code "77") (name "/RF-IN") (class "Default")
      (node (ref "E1") (pin "SIG") (pinfunction "SIGNAL_SIG") (pintype "bidirectional"))
      (node (ref "FB1") (pin "1") (pinfunction "1_1") (pintype "passive"))
      (node (ref "U11") (pin "P$11") (pinfunction "RF_IN_P$11") (pintype "bidirectional"))
    )
    (net (code "78") (name "/RGB_0") (class "Default")
      (node (ref "U2") (pin "39") (pinfunction "RGB0_39") (pintype "bidirectional"))
      (node (ref "U9") (pin "P$2") (pinfunction "P$2_P$2") (pintype "bidirectional"))
    )
    (net (code "79") (name "/RGB_1") (class "Default")
      (node (ref "U2") (pin "40") (pinfunction "RGB1_40") (pintype "bidirectional"))
      (node (ref "U9") (pin "P$3") (pinfunction "P$3_P$3") (pintype "bidirectional"))
    )
    (net (code "80") (name "/RGB_2") (class "Default")
      (node (ref "U2") (pin "41") (pinfunction "RGB2_41") (pintype "bidirectional"))
      (node (ref "U9") (pin "P$4") (pinfunction "P$4_P$4") (pintype "bidirectional"))
    )
    (net (code "81") (name "/USB_D+") (class "Default")
      (node (ref "J1") (pin "A6") (pinfunction "DP1_A6") (pintype "bidirectional"))
      (node (ref "J1") (pin "B6") (pinfunction "DP2_B6") (pintype "bidirectional"))
      (node (ref "U1") (pin "26") (pinfunction "GPIO20/USB_D+_26") (pintype "passive"))
    )
    (net (code "82") (name "/USB_D-") (class "Default")
      (node (ref "J1") (pin "A7") (pinfunction "DN1_A7") (pintype "bidirectional"))
      (node (ref "J1") (pin "B7") (pinfunction "DN2_B7") (pintype "bidirectional"))
      (node (ref "U1") (pin "25") (pinfunction "GPIO19/US_D-_25") (pintype "passive"))
    )
    (net (code "83") (name "/VDD_CPU_MAIN") (class "Default")
      (node (ref "C34") (pin "1") (pinfunction "1_1") (pintype "passive"))
      (node (ref "C35") (pin "1") (pinfunction "1_1") (pintype "passive"))
      (node (ref "L1") (pin "2") (pinfunction "2_2") (pintype "passive"))
      (node (ref "U1") (pin "3") (pinfunction "VDD3P3_3") (pintype "passive"))
      (node (ref "U1") (pin "4") (pinfunction "VDD3P3_2_4") (pintype "passive"))
    )
    (net (code "84") (name "/XTAL_N") (class "Default")
      (node (ref "C7") (pin "1") (pinfunction "1_1") (pintype "passive"))
      (node (ref "U1") (pin "52") (pinfunction "XTAL_N_52") (pintype "passive"))
      (node (ref "U5") (pin "OUT/IN") (pinfunction "OUT/IN_OUT/IN") (pintype "bidirectional"))
    )
    (net (code "85") (name "/XTAL_P") (class "Default")
      (node (ref "R3") (pin "1") (pinfunction "1_1") (pintype "passive"))
      (node (ref "U1") (pin "53") (pinfunction "XTAL_P_53") (pintype "passive"))
    )
    (net (code "86") (name "GND") (class "Default")
      (node (ref "C1") (pin "2") (pinfunction "2_2") (pintype "passive"))
      (node (ref "C10") (pin "2") (pinfunction "2_2") (pintype "passive"))
      (node (ref "C11") (pin "2") (pinfunction "2_2") (pintype "passive"))
      (node (ref "C12") (pin "2") (pinfunction "2_2") (pintype "passive"))
      (node (ref "C13") (pin "2") (pinfunction "2_2") (pintype "passive"))
      (node (ref "C14") (pin "2") (pinfunction "2_2") (pintype "passive"))
      (node (ref "C15") (pin "2") (pinfunction "2_2") (pintype "passive"))
      (node (ref "C16") (pin "2") (pinfunction "2_2") (pintype "passive"))
      (node (ref "C17") (pin "2") (pinfunction "2_2") (pintype "passive"))
      (node (ref "C18") (pin "2") (pinfunction "2_2") (pintype "passive"))
      (node (ref "C2") (pin "2") (pinfunction "2_2") (pintype "passive"))
      (node (ref "C20") (pin "2") (pinfunction "2_2") (pintype "passive"))
      (node (ref "C25") (pin "2") (pinfunction "2_2") (pintype "passive"))
      (node (ref "C27") (pin "2") (pinfunction "2_2") (pintype "passive"))
      (node (ref "C3") (pin "2") (pinfunction "2_2") (pintype "passive"))
      (node (ref "C32") (pin "2") (pinfunction "2_2") (pintype "passive"))
      (node (ref "C33") (pin "2") (pinfunction "2_2") (pintype "passive"))
      (node (ref "C34") (pin "2") (pinfunction "2_2") (pintype "passive"))
      (node (ref "C35") (pin "2") (pinfunction "2_2") (pintype "passive"))
      (node (ref "C37") (pin "2") (pinfunction "2_2") (pintype "passive"))
      (node (ref "C38") (pin "2") (pinfunction "2_2") (pintype "passive"))
      (node (ref "C39") (pin "2") (pinfunction "2_2") (pintype "passive"))
      (node (ref "C4") (pin "2") (pinfunction "2_2") (pintype "passive"))
      (node (ref "C40") (pin "2") (pinfunction "2_2") (pintype "passive"))
      (node (ref "C41") (pin "2") (pinfunction "2_2") (pintype "passive"))
      (node (ref "C42") (pin "2") (pinfunction "2_2") (pintype "passive"))
      (node (ref "C43") (pin "2") (pinfunction "2_2") (pintype "passive"))
      (node (ref "C44") (pin "2") (pinfunction "2_2") (pintype "passive"))
      (node (ref "C45") (pin "2") (pinfunction "2_2") (pintype "passive"))
      (node (ref "C46") (pin "2") (pinfunction "2_2") (pintype "passive"))
      (node (ref "C48") (pin "2") (pinfunction "2_2") (pintype "passive"))
      (node (ref "C49") (pin "2") (pinfunction "2_2") (pintype "passive"))
      (node (ref "C5") (pin "2") (pinfunction "2_2") (pintype "passive"))
      (node (ref "C50") (pin "2") (pinfunction "2_2") (pintype "passive"))
      (node (ref "C52") (pin "2") (pinfunction "2_2") (pintype "passive"))
      (node (ref "C6") (pin "2") (pinfunction "2_2") (pintype "passive"))
      (node (ref "C7") (pin "2") (pinfunction "2_2") (pintype "passive"))
      (node (ref "C8") (pin "2") (pinfunction "2_2") (pintype "passive"))
      (node (ref "C9") (pin "2") (pinfunction "2_2") (pintype "passive"))
      (node (ref "D9") (pin "C") (pinfunction "C_C") (pintype "passive"))
      (node (ref "E1") (pin "GND@0") (pinfunction "GND_GND@0") (pintype "bidirectional"))
      (node (ref "E1") (pin "GND@1") (pinfunction "GND_GND@1") (pintype "bidirectional"))
      (node (ref "E1") (pin "GND@2") (pinfunction "GND_GND@2") (pintype "bidirectional"))
      (node (ref "E1") (pin "GND@3") (pinfunction "GND_GND@3") (pintype "bidirectional"))
      (node (ref "E2") (pin "GND@0") (pinfunction "GND_GND@0") (pintype "bidirectional"))
      (node (ref "E2") (pin "GND@1") (pinfunction "GND_GND@1") (pintype "bidirectional"))
      (node (ref "E2") (pin "GND@2") (pinfunction "GND_GND@2") (pintype "bidirectional"))
      (node (ref "E2") (pin "GND@3") (pinfunction "GND_GND@3") (pintype "bidirectional"))
      (node (ref "J1") (pin "A1/B12") (pinfunction "GND_A1/B12") (pintype "power_in"))
      (node (ref "J1") (pin "B1/A12") (pinfunction "GND_B1/A12") (pintype "power_in"))
      (node (ref "J1") (pin "S1") (pinfunction "GND_S1") (pintype "power_in"))
      (node (ref "J1") (pin "S2") (pinfunction "GND_S2") (pintype "power_in"))
      (node (ref "J1") (pin "S3") (pinfunction "GND_S3") (pintype "power_in"))
      (node (ref "J1") (pin "S4") (pinfunction "GND_S4") (pintype "power_in"))
      (node (ref "Q1") (pin "2") (pinfunction "S_2") (pintype "passive"))
      (node (ref "Q10") (pin "2") (pinfunction "S_2") (pintype "passive"))
      (node (ref "Q11") (pin "2") (pinfunction "S_2") (pintype "passive"))
      (node (ref "Q12") (pin "2") (pinfunction "S_2") (pintype "passive"))
      (node (ref "Q13") (pin "2") (pinfunction "S_2") (pintype "passive"))
      (node (ref "Q14") (pin "2") (pinfunction "S_2") (pintype "passive"))
      (node (ref "Q15") (pin "2") (pinfunction "S_2") (pintype "passive"))
      (node (ref "Q16") (pin "2") (pinfunction "S_2") (pintype "passive"))
      (node (ref "Q2") (pin "2") (pinfunction "S_2") (pintype "passive"))
      (node (ref "Q3") (pin "2") (pinfunction "S_2") (pintype "passive"))
      (node (ref "Q4") (pin "2") (pinfunction "S_2") (pintype "passive"))
      (node (ref "Q5") (pin "2") (pinfunction "S_2") (pintype "passive"))
      (node (ref "Q6") (pin "2") (pinfunction "S_2") (pintype "passive"))
      (node (ref "Q7") (pin "2") (pinfunction "S_2") (pintype "passive"))
      (node (ref "Q8") (pin "2") (pinfunction "S_2") (pintype "passive"))
      (node (ref "Q9") (pin "2") (pinfunction "S_2") (pintype "passive"))
      (node (ref "R1") (pin "1") (pinfunction "1_1") (pintype "passive"))
      (node (ref "R10") (pin "2") (pinfunction "2_2") (pintype "passive"))
      (node (ref "R11") (pin "2") (pinfunction "2_2") (pintype "passive"))
      (node (ref "R12") (pin "1") (pinfunction "1_1") (pintype "passive"))
      (node (ref "R13") (pin "2") (pinfunction "2_2") (pintype "passive"))
      (node (ref "R14") (pin "2") (pinfunction "2_2") (pintype "passive"))
      (node (ref "R19") (pin "2") (pinfunction "2_2") (pintype "passive"))
      (node (ref "R21") (pin "2") (pinfunction "2_2") (pintype "passive"))
      (node (ref "R28") (pin "1") (pinfunction "1_1") (pintype "passive"))
      (node (ref "R4") (pin "2") (pinfunction "2_2") (pintype "passive"))
      (node (ref "R48") (pin "2") (pinfunction "2_2") (pintype "passive"))
      (node (ref "R5") (pin "2") (pinfunction "2_2") (pintype "passive"))
      (node (ref "R67") (pin "2") (pinfunction "2_2") (pintype "passive"))
      (node (ref "R68") (pin "2") (pinfunction "2_2") (pintype "passive"))
      (node (ref "R73") (pin "2") (pinfunction "2_2") (pintype "passive"))
      (node (ref "R74") (pin "2") (pinfunction "2_2") (pintype "passive"))
      (node (ref "R83") (pin "2") (pinfunction "2_2") (pintype "passive"))
      (node (ref "R93") (pin "2") (pinfunction "2_2") (pintype "passive"))
      (node (ref "R96") (pin "1") (pinfunction "1_1") (pintype "passive"))
      (node (ref "R97") (pin "1") (pinfunction "1_1") (pintype "passive"))
      (node (ref "R99") (pin "1") (pinfunction "1_1") (pintype "passive"))
      (node (ref "U$1") (pin "P$1") (pinfunction "P$1_P$1") (pintype "bidirectional"))
      (node (ref "U$2") (pin "GND") (pinfunction "GND_GND") (pintype "bidirectional"))
      (node (ref "U1") (pin "57") (pinfunction "EPAD_57") (pintype "passive"))
      (node (ref "U10") (pin "1") (pinfunction "1_1") (pintype "passive"))
      (node (ref "U11") (pin "P$1") (pinfunction "GND1_P$1") (pintype "bidirectional"))
      (node (ref "U11") (pin "P$10") (pinfunction "GND2_P$10") (pintype "bidirectional"))
      (node (ref "U11") (pin "P$12") (pinfunction "GND3_P$12") (pintype "bidirectional"))
      (node (ref "U2") (pin "PAD") (pinfunction "PAD_PAD") (pintype "passive"))
      (node (ref "U3") (pin "2") (pinfunction "GND_2") (pintype "passive"))
      (node (ref "U4") (pin "2") (pinfunction "GND_2") (pintype "power_in"))
      (node (ref "U4") (pin "3") (pinfunction "~{EN}_3") (pintype "input"))
      (node (ref "U5") (pin "GND-A") (pinfunction "GND_GND-A") (pintype "power_in"))
      (node (ref "U5") (pin "GND-B") (pinfunction "GND_GND-B") (pintype "power_in"))
      (node (ref "U6") (pin "2") (pinfunction "GND_2") (pintype "passive"))
      (node (ref "U7") (pin "2") (pinfunction "GND_2") (pintype "power_in"))
    )
    (net (code "87") (name "Net-(C6-Pad1)") (class "Default")
      (node (ref "C6") (pin "1") (pinfunction "1_1") (pintype "passive"))
      (node (ref "R3") (pin "2") (pinfunction "2_2") (pintype "passive"))
      (node (ref "U5") (pin "IN/OUT") (pinfunction "IN/OUT_IN/OUT") (pintype "bidirectional"))
    )
    (net (code "88") (name "Net-(C25-Pad1)") (class "Default")
      (node (ref "C25") (pin "1") (pinfunction "1_1") (pintype "passive"))
      (node (ref "FB1") (pin "2") (pinfunction "2_2") (pintype "passive"))
      (node (ref "R84") (pin "2") (pinfunction "2_2") (pintype "passive"))
    )
    (net (code "89") (name "Net-(D1-PadA)") (class "Default")
      (node (ref "D1") (pin "A") (pinfunction "A_A") (pintype "passive"))
      (node (ref "R23") (pin "2") (pinfunction "2_2") (pintype "passive"))
    )
    (net (code "90") (name "Net-(D2-PadA)") (class "Default")
      (node (ref "D2") (pin "A") (pinfunction "A_A") (pintype "passive"))
      (node (ref "R2") (pin "1") (pinfunction "1_1") (pintype "passive"))
    )
    (net (code "91") (name "Net-(D3-C)") (class "Default")
      (node (ref "D3") (pin "1") (pinfunction "C_1") (pintype "passive"))
      (node (ref "R46") (pin "2") (pinfunction "2_2") (pintype "passive"))
    )
    (net (code "92") (name "Net-(D4-PadA)") (class "Default")
      (node (ref "D4") (pin "A") (pinfunction "A_A") (pintype "passive"))
      (node (ref "R6") (pin "1") (pinfunction "1_1") (pintype "passive"))
    )
    (net (code "93") (name "Net-(D5-PadA)") (class "Default")
      (node (ref "D5") (pin "A") (pinfunction "A_A") (pintype "passive"))
      (node (ref "R7") (pin "1") (pinfunction "1_1") (pintype "passive"))
    )
    (net (code "94") (name "Net-(D6-PadA)") (class "Default")
      (node (ref "D6") (pin "A") (pinfunction "A_A") (pintype "passive"))
      (node (ref "R8") (pin "1") (pinfunction "1_1") (pintype "passive"))
    )
    (net (code "95") (name "Net-(D7-PadA)") (class "Default")
      (node (ref "D7") (pin "A") (pinfunction "A_A") (pintype "passive"))
      (node (ref "R9") (pin "1") (pinfunction "1_1") (pintype "passive"))
    )
    (net (code "96") (name "Net-(D8-PadA)") (class "Default")
      (node (ref "D8") (pin "A") (pinfunction "A_A") (pintype "passive"))
      (node (ref "R30") (pin "1") (pinfunction "1_1") (pintype "passive"))
    )
    (net (code "97") (name "Net-(D9-PadA)") (class "Default")
      (node (ref "D9") (pin "A") (pinfunction "A_A") (pintype "passive"))
      (node (ref "R47") (pin "1") (pinfunction "1_1") (pintype "passive"))
    )
    (net (code "98") (name "Net-(D10-PadA)") (class "Default")
      (node (ref "D10") (pin "A") (pinfunction "A_A") (pintype "passive"))
      (node (ref "R31") (pin "1") (pinfunction "1_1") (pintype "passive"))
    )
    (net (code "99") (name "Net-(D11-PadA)") (class "Default")
      (node (ref "D11") (pin "A") (pinfunction "A_A") (pintype "passive"))
      (node (ref "R32") (pin "1") (pinfunction "1_1") (pintype "passive"))
    )
    (net (code "100") (name "Net-(D12-PadA)") (class "Default")
      (node (ref "D12") (pin "A") (pinfunction "A_A") (pintype "passive"))
      (node (ref "R15") (pin "1") (pinfunction "1_1") (pintype "passive"))
    )
    (net (code "101") (name "Net-(D13-PadA)") (class "Default")
      (node (ref "D13") (pin "A") (pinfunction "A_A") (pintype "passive"))
      (node (ref "R16") (pin "1") (pinfunction "1_1") (pintype "passive"))
    )
    (net (code "102") (name "Net-(D14-PadA)") (class "Default")
      (node (ref "D14") (pin "A") (pinfunction "A_A") (pintype "passive"))
      (node (ref "R17") (pin "1") (pinfunction "1_1") (pintype "passive"))
    )
    (net (code "103") (name "Net-(D15-PadA)") (class "Default")
      (node (ref "D15") (pin "A") (pinfunction "A_A") (pintype "passive"))
      (node (ref "R18") (pin "1") (pinfunction "1_1") (pintype "passive"))
    )
    (net (code "104") (name "Net-(D16-PadA)") (class "Default")
      (node (ref "D16") (pin "A") (pinfunction "A_A") (pintype "passive"))
      (node (ref "R37") (pin "1") (pinfunction "1_1") (pintype "passive"))
    )
    (net (code "105") (name "Net-(D17-PadA)") (class "Default")
      (node (ref "D17") (pin "A") (pinfunction "A_A") (pintype "passive"))
      (node (ref "R38") (pin "1") (pinfunction "1_1") (pintype "passive"))
    )
    (net (code "106") (name "Net-(D18-PadA)") (class "Default")
      (node (ref "D18") (pin "A") (pinfunction "A_A") (pintype "passive"))
      (node (ref "R39") (pin "1") (pinfunction "1_1") (pintype "passive"))
    )
    (net (code "107") (name "Net-(D19-PadA)") (class "Default")
      (node (ref "D19") (pin "A") (pinfunction "A_A") (pintype "passive"))
      (node (ref "R40") (pin "1") (pinfunction "1_1") (pintype "passive"))
    )
    (net (code "108") (name "Net-(D20-PadA)") (class "Default")
      (node (ref "D20") (pin "A") (pinfunction "A_A") (pintype "passive"))
      (node (ref "R24") (pin "1") (pinfunction "1_1") (pintype "passive"))
    )
    (net (code "109") (name "Net-(D21-PadA)") (class "Default")
      (node (ref "D21") (pin "A") (pinfunction "A_A") (pintype "passive"))
      (node (ref "R25") (pin "1") (pinfunction "1_1") (pintype "passive"))
    )
    (net (code "110") (name "Net-(D22-PadA)") (class "Default")
      (node (ref "D22") (pin "A") (pinfunction "A_A") (pintype "passive"))
      (node (ref "R26") (pin "1") (pinfunction "1_1") (pintype "passive"))
    )
    (net (code "111") (name "Net-(D23-PadA)") (class "Default")
      (node (ref "D23") (pin "A") (pinfunction "A_A") (pintype "passive"))
      (node (ref "R27") (pin "1") (pinfunction "1_1") (pintype "passive"))
    )
    (net (code "112") (name "Net-(D24-PadA)") (class "Default")
      (node (ref "D24") (pin "A") (pinfunction "A_A") (pintype "passive"))
      (node (ref "R41") (pin "1") (pinfunction "1_1") (pintype "passive"))
    )
    (net (code "113") (name "Net-(D25-PadA)") (class "Default")
      (node (ref "D25") (pin "A") (pinfunction "A_A") (pintype "passive"))
      (node (ref "R56") (pin "1") (pinfunction "1_1") (pintype "passive"))
    )
    (net (code "114") (name "Net-(D26-PadA)") (class "Default")
      (node (ref "D26") (pin "A") (pinfunction "A_A") (pintype "passive"))
      (node (ref "R57") (pin "1") (pinfunction "1_1") (pintype "passive"))
    )
    (net (code "115") (name "Net-(D27-PadA)") (class "Default")
      (node (ref "D27") (pin "A") (pinfunction "A_A") (pintype "passive"))
      (node (ref "R58") (pin "1") (pinfunction "1_1") (pintype "passive"))
    )
    (net (code "116") (name "Net-(D28-PadA)") (class "Default")
      (node (ref "D28") (pin "A") (pinfunction "A_A") (pintype "passive"))
      (node (ref "R33") (pin "1") (pinfunction "1_1") (pintype "passive"))
    )
    (net (code "117") (name "Net-(D29-PadA)") (class "Default")
      (node (ref "D29") (pin "A") (pinfunction "A_A") (pintype "passive"))
      (node (ref "R34") (pin "1") (pinfunction "1_1") (pintype "passive"))
    )
    (net (code "118") (name "Net-(D30-PadA)") (class "Default")
      (node (ref "D30") (pin "A") (pinfunction "A_A") (pintype "passive"))
      (node (ref "R35") (pin "1") (pinfunction "1_1") (pintype "passive"))
    )
    (net (code "119") (name "Net-(D31-PadA)") (class "Default")
      (node (ref "D31") (pin "A") (pinfunction "A_A") (pintype "passive"))
      (node (ref "R36") (pin "1") (pinfunction "1_1") (pintype "passive"))
    )
    (net (code "120") (name "Net-(D32-PadA)") (class "Default")
      (node (ref "D32") (pin "A") (pinfunction "A_A") (pintype "passive"))
      (node (ref "R59") (pin "1") (pinfunction "1_1") (pintype "passive"))
    )
    (net (code "121") (name "Net-(D33-PadA)") (class "Default")
      (node (ref "D33") (pin "A") (pinfunction "A_A") (pintype "passive"))
      (node (ref "R64") (pin "1") (pinfunction "1_1") (pintype "passive"))
    )
    (net (code "122") (name "Net-(D34-PadA)") (class "Default")
      (node (ref "D34") (pin "A") (pinfunction "A_A") (pintype "passive"))
      (node (ref "R65") (pin "1") (pinfunction "1_1") (pintype "passive"))
    )
    (net (code "123") (name "Net-(D35-PadA)") (class "Default")
      (node (ref "D35") (pin "A") (pinfunction "A_A") (pintype "passive"))
      (node (ref "R66") (pin "1") (pinfunction "1_1") (pintype "passive"))
    )
    (net (code "124") (name "Net-(D36-PadA)") (class "Default")
      (node (ref "D36") (pin "A") (pinfunction "A_A") (pintype "passive"))
      (node (ref "R42") (pin "1") (pinfunction "1_1") (pintype "passive"))
    )
    (net (code "125") (name "Net-(D37-PadA)") (class "Default")
      (node (ref "D37") (pin "A") (pinfunction "A_A") (pintype "passive"))
      (node (ref "R43") (pin "1") (pinfunction "1_1") (pintype "passive"))
    )
    (net (code "126") (name "Net-(D38-PadA)") (class "Default")
      (node (ref "D38") (pin "A") (pinfunction "A_A") (pintype "passive"))
      (node (ref "R44") (pin "1") (pinfunction "1_1") (pintype "passive"))
    )
    (net (code "127") (name "Net-(D39-PadA)") (class "Default")
      (node (ref "D39") (pin "A") (pinfunction "A_A") (pintype "passive"))
      (node (ref "R45") (pin "1") (pinfunction "1_1") (pintype "passive"))
    )
    (net (code "128") (name "Net-(D40-PadA)") (class "Default")
      (node (ref "D40") (pin "A") (pinfunction "A_A") (pintype "passive"))
      (node (ref "R75") (pin "1") (pinfunction "1_1") (pintype "passive"))
    )
    (net (code "129") (name "Net-(D41-PadA)") (class "Default")
      (node (ref "D41") (pin "A") (pinfunction "A_A") (pintype "passive"))
      (node (ref "R76") (pin "1") (pinfunction "1_1") (pintype "passive"))
    )
    (net (code "130") (name "Net-(D42-PadA)") (class "Default")
      (node (ref "D42") (pin "A") (pinfunction "A_A") (pintype "passive"))
      (node (ref "R77") (pin "1") (pinfunction "1_1") (pintype "passive"))
    )
    (net (code "131") (name "Net-(D43-PadA)") (class "Default")
      (node (ref "D43") (pin "A") (pinfunction "A_A") (pintype "passive"))
      (node (ref "R82") (pin "1") (pinfunction "1_1") (pintype "passive"))
    )
    (net (code "132") (name "Net-(D44-PadA)") (class "Default")
      (node (ref "D44") (pin "A") (pinfunction "A_A") (pintype "passive"))
      (node (ref "R51") (pin "1") (pinfunction "1_1") (pintype "passive"))
    )
    (net (code "133") (name "Net-(D45-PadA)") (class "Default")
      (node (ref "D45") (pin "A") (pinfunction "A_A") (pintype "passive"))
      (node (ref "R52") (pin "1") (pinfunction "1_1") (pintype "passive"))
    )
    (net (code "134") (name "Net-(D46-PadA)") (class "Default")
      (node (ref "D46") (pin "A") (pinfunction "A_A") (pintype "passive"))
      (node (ref "R53") (pin "1") (pinfunction "1_1") (pintype "passive"))
    )
    (net (code "135") (name "Net-(D47-PadA)") (class "Default")
      (node (ref "D47") (pin "A") (pinfunction "A_A") (pintype "passive"))
      (node (ref "R54") (pin "1") (pinfunction "1_1") (pintype "passive"))
    )
    (net (code "136") (name "Net-(D48-PadA)") (class "Default")
      (node (ref "D48") (pin "A") (pinfunction "A_A") (pintype "passive"))
      (node (ref "R85") (pin "1") (pinfunction "1_1") (pintype "passive"))
    )
    (net (code "137") (name "Net-(D49-PadA)") (class "Default")
      (node (ref "D49") (pin "A") (pinfunction "A_A") (pintype "passive"))
      (node (ref "R86") (pin "1") (pinfunction "1_1") (pintype "passive"))
    )
    (net (code "138") (name "Net-(D50-PadA)") (class "Default")
      (node (ref "D50") (pin "A") (pinfunction "A_A") (pintype "passive"))
      (node (ref "R91") (pin "1") (pinfunction "1_1") (pintype "passive"))
    )
    (net (code "139") (name "Net-(D51-PadA)") (class "Default")
      (node (ref "D51") (pin "A") (pinfunction "A_A") (pintype "passive"))
      (node (ref "R92") (pin "1") (pinfunction "1_1") (pintype "passive"))
    )
    (net (code "140") (name "Net-(D52-PadA)") (class "Default")
      (node (ref "D52") (pin "A") (pinfunction "A_A") (pintype "passive"))
      (node (ref "R60") (pin "1") (pinfunction "1_1") (pintype "passive"))
    )
    (net (code "141") (name "Net-(D53-PadA)") (class "Default")
      (node (ref "D53") (pin "A") (pinfunction "A_A") (pintype "passive"))
      (node (ref "R61") (pin "1") (pinfunction "1_1") (pintype "passive"))
    )
    (net (code "142") (name "Net-(D54-PadA)") (class "Default")
      (node (ref "D54") (pin "A") (pinfunction "A_A") (pintype "passive"))
      (node (ref "R62") (pin "1") (pinfunction "1_1") (pintype "passive"))
    )
    (net (code "143") (name "Net-(D55-PadA)") (class "Default")
      (node (ref "D55") (pin "A") (pinfunction "A_A") (pintype "passive"))
      (node (ref "R63") (pin "1") (pinfunction "1_1") (pintype "passive"))
    )
    (net (code "144") (name "Net-(D60-PadA)") (class "Default")
      (node (ref "D60") (pin "A") (pinfunction "A_A") (pintype "passive"))
      (node (ref "R69") (pin "1") (pinfunction "1_1") (pintype "passive"))
    )
    (net (code "145") (name "Net-(D61-PadA)") (class "Default")
      (node (ref "D61") (pin "A") (pinfunction "A_A") (pintype "passive"))
      (node (ref "R70") (pin "1") (pinfunction "1_1") (pintype "passive"))
    )
    (net (code "146") (name "Net-(D62-PadA)") (class "Default")
      (node (ref "D62") (pin "A") (pinfunction "A_A") (pintype "passive"))
      (node (ref "R71") (pin "1") (pinfunction "1_1") (pintype "passive"))
    )
    (net (code "147") (name "Net-(D63-PadA)") (class "Default")
      (node (ref "D63") (pin "A") (pinfunction "A_A") (pintype "passive"))
      (node (ref "R72") (pin "1") (pinfunction "1_1") (pintype "passive"))
    )
    (net (code "148") (name "Net-(D68-PadA)") (class "Default")
      (node (ref "D68") (pin "A") (pinfunction "A_A") (pintype "passive"))
      (node (ref "R78") (pin "1") (pinfunction "1_1") (pintype "passive"))
    )
    (net (code "149") (name "Net-(D69-PadA)") (class "Default")
      (node (ref "D69") (pin "A") (pinfunction "A_A") (pintype "passive"))
      (node (ref "R79") (pin "1") (pinfunction "1_1") (pintype "passive"))
    )
    (net (code "150") (name "Net-(D70-PadA)") (class "Default")
      (node (ref "D70") (pin "A") (pinfunction "A_A") (pintype "passive"))
      (node (ref "R80") (pin "1") (pinfunction "1_1") (pintype "passive"))
    )
    (net (code "151") (name "Net-(D71-PadA)") (class "Default")
      (node (ref "D71") (pin "A") (pinfunction "A_A") (pintype "passive"))
      (node (ref "R81") (pin "1") (pinfunction "1_1") (pintype "passive"))
    )
    (net (code "152") (name "Net-(D76-PadA)") (class "Default")
      (node (ref "D76") (pin "A") (pinfunction "A_A") (pintype "passive"))
      (node (ref "R87") (pin "1") (pinfunction "1_1") (pintype "passive"))
    )
    (net (code "153") (name "Net-(D77-PadA)") (class "Default")
      (node (ref "D77") (pin "A") (pinfunction "A_A") (pintype "passive"))
      (node (ref "R88") (pin "1") (pinfunction "1_1") (pintype "passive"))
    )
    (net (code "154") (name "Net-(D78-PadA)") (class "Default")
      (node (ref "D78") (pin "A") (pinfunction "A_A") (pintype "passive"))
      (node (ref "R89") (pin "1") (pinfunction "1_1") (pintype "passive"))
    )
    (net (code "155") (name "Net-(D79-PadA)") (class "Default")
      (node (ref "D79") (pin "A") (pinfunction "A_A") (pintype "passive"))
      (node (ref "R90") (pin "1") (pinfunction "1_1") (pintype "passive"))
    )
    (net (code "156") (name "Net-(J1-CC1)") (class "Default")
      (node (ref "J1") (pin "A5") (pinfunction "CC1_A5") (pintype "bidirectional"))
      (node (ref "R97") (pin "2") (pinfunction "2_2") (pintype "passive"))
    )
    (net (code "157") (name "Net-(J1-CC2)") (class "Default")
      (node (ref "J1") (pin "B5") (pinfunction "CC2_B5") (pintype "bidirectional"))
      (node (ref "R96") (pin "2") (pinfunction "2_2") (pintype "passive"))
    )
    (net (code "158") (name "Net-(U6-OUT)") (class "Default")
      (node (ref "C15") (pin "1") (pinfunction "1_1") (pintype "passive"))
      (node (ref "U$2") (pin "VDD") (pinfunction "VDD_VDD") (pintype "bidirectional"))
      (node (ref "U6") (pin "5") (pinfunction "OUT_5") (pintype "output"))
    )
    (net (code "159") (name "Net-(U11-RXD)") (class "Default")
      (node (ref "R49") (pin "2") (pinfunction "2_2") (pintype "passive"))
      (node (ref "U11") (pin "P$3") (pinfunction "RXD_P$3") (pintype "bidirectional"))
    )
    (net (code "160") (name "Net-(U11-TIMEPULSE)") (class "Default")
      (node (ref "R50") (pin "2") (pinfunction "2_2") (pintype "passive"))
      (node (ref "U11") (pin "P$4") (pinfunction "TIMEPULSE_P$4") (pintype "bidirectional"))
    )
    (net (code "161") (name "Net-(U11-TXD)") (class "Default")
      (node (ref "R55") (pin "2") (pinfunction "2_2") (pintype "passive"))
      (node (ref "U11") (pin "P$2") (pinfunction "TXD_P$2") (pintype "bidirectional"))
    )
    (net (code "162") (name "Net-(U11-VCC_RF)") (class "Default")
      (node (ref "R84") (pin "1") (pinfunction "1_1") (pintype "passive"))
      (node (ref "U11") (pin "P$14") (pinfunction "VCC_RF_P$14") (pintype "bidirectional"))
    )
    (net (code "163") (name "unconnected-(J1-SBU1-PadA8)") (class "Default")
      (node (ref "J1") (pin "A8") (pinfunction "SBU1_A8") (pintype "bidirectional"))
    )
    (net (code "164") (name "unconnected-(J1-SBU2-PadB8)") (class "Default")
      (node (ref "J1") (pin "B8") (pinfunction "SBU2_B8") (pintype "bidirectional"))
    )
    (net (code "165") (name "unconnected-(U1-DAC_1-Pad23)") (class "Default")
      (node (ref "U1") (pin "23") (pinfunction "DAC_1_23") (pintype "passive"))
    )
    (net (code "166") (name "unconnected-(U1-DAC_2-Pad24)") (class "Default")
      (node (ref "U1") (pin "24") (pinfunction "DAC_2_24") (pintype "passive"))
    )
    (net (code "167") (name "unconnected-(U1-GPIO1-Pad6)") (class "Default")
      (node (ref "U1") (pin "6") (pinfunction "GPIO1_6") (pintype "passive"))
    )
    (net (code "168") (name "unconnected-(U1-GPIO3-Pad8)") (class "Default")
      (node (ref "U1") (pin "8") (pinfunction "GPIO3_8") (pintype "passive"))
    )
    (net (code "169") (name "unconnected-(U1-GPIO4-Pad9)") (class "Default")
      (node (ref "U1") (pin "9") (pinfunction "GPIO4_9") (pintype "passive"))
    )
    (net (code "170") (name "unconnected-(U1-GPIO5-Pad10)") (class "Default")
      (node (ref "U1") (pin "10") (pinfunction "GPIO5_10") (pintype "passive"))
    )
    (net (code "171") (name "unconnected-(U1-GPIO6-Pad11)") (class "Default")
      (node (ref "U1") (pin "11") (pinfunction "GPIO6_11") (pintype "passive"))
    )
    (net (code "172") (name "unconnected-(U1-GPIO7-Pad12)") (class "Default")
      (node (ref "U1") (pin "12") (pinfunction "GPIO7_12") (pintype "passive"))
    )
    (net (code "173") (name "unconnected-(U1-GPIO8-Pad13)") (class "Default")
      (node (ref "U1") (pin "13") (pinfunction "GPIO8_13") (pintype "passive"))
    )
    (net (code "174") (name "unconnected-(U1-GPIO21-Pad28)") (class "Default")
      (node (ref "U1") (pin "28") (pinfunction "GPIO21_28") (pintype "passive"))
    )
    (net (code "175") (name "unconnected-(U1-GPIO45-Pad50)") (class "Default")
      (node (ref "U1") (pin "50") (pinfunction "GPIO45_50") (pintype "passive"))
    )
    (net (code "176") (name "unconnected-(U1-GPIO46-Pad55)") (class "Default")
      (node (ref "U1") (pin "55") (pinfunction "GPIO46_55") (pintype "passive"))
    )
    (net (code "177") (name "unconnected-(U1-MTCK-Pad43)") (class "Default")
      (node (ref "U1") (pin "43") (pinfunction "MTCK_43") (pintype "passive"))
    )
    (net (code "178") (name "unconnected-(U1-MTD0-Pad44)") (class "Default")
      (node (ref "U1") (pin "44") (pinfunction "MTD0_44") (pintype "passive"))
    )
    (net (code "179") (name "unconnected-(U1-MTDI-Pad46)") (class "Default")
      (node (ref "U1") (pin "46") (pinfunction "MTDI_46") (pintype "passive"))
    )
    (net (code "180") (name "unconnected-(U1-MTMS-Pad47)") (class "Default")
      (node (ref "U1") (pin "47") (pinfunction "MTMS_47") (pintype "passive"))
    )
    (net (code "181") (name "unconnected-(U1-SPICS1-Pad29)") (class "Default")
      (node (ref "U1") (pin "29") (pinfunction "SPICS1_29") (pintype "passive"))
    )
    (net (code "182") (name "unconnected-(U1-XTAL_32K_N-Pad22)") (class "Default")
      (node (ref "U1") (pin "22") (pinfunction "XTAL_32K_N_22") (pintype "passive"))
    )
    (net (code "183") (name "unconnected-(U1-XTAL_32K_P-Pad21)") (class "Default")
      (node (ref "U1") (pin "21") (pinfunction "XTAL_32K_P_21") (pintype "passive"))
    )
    (net (code "184") (name "unconnected-(U3-NC{slash}ADJ-Pad4)") (class "Default")
      (node (ref "U3") (pin "4") (pinfunction "NC/ADJ_4") (pintype "no_connect"))
    )
    (net (code "185") (name "unconnected-(U6-NC{slash}ADJ-Pad4)") (class "Default")
      (node (ref "U6") (pin "4") (pinfunction "NC/ADJ_4") (pintype "no_connect"))
    )
    (net (code "186") (name "unconnected-(U11-LNA_EN-PadP$13)") (class "Default")
      (node (ref "U11") (pin "P$13") (pinfunction "LNA_EN_P$13") (pintype "bidirectional"))
    )
    (net (code "187") (name "unconnected-(U11-SAFEBOOT_N-PadP$18)") (class "Default")
      (node (ref "U11") (pin "P$18") (pinfunction "SAFEBOOT_N_P$18") (pintype "bidirectional"))
    )
    (net (code "188") (name "unconnected-(U11-SCL-PadP$17)") (class "Default")
      (node (ref "U11") (pin "P$17") (pinfunction "SCL_P$17") (pintype "bidirectional"))
    )
    (net (code "189") (name "unconnected-(U11-SDA-PadP$16)") (class "Default")
      (node (ref "U11") (pin "P$16") (pinfunction "SDA_P$16") (pintype "bidirectional"))
    )
    (net (code "190") (name "unconnected-(U11-VIO_SEL-PadP$15)") (class "Default")
      (node (ref "U11") (pin "P$15") (pinfunction "VIO_SEL_P$15") (pintype "bidirectional"))
    )
  )
)
